# Netzteil_Darlington_v2.net
KiCad netlist of a schematic drawn in EAGLE
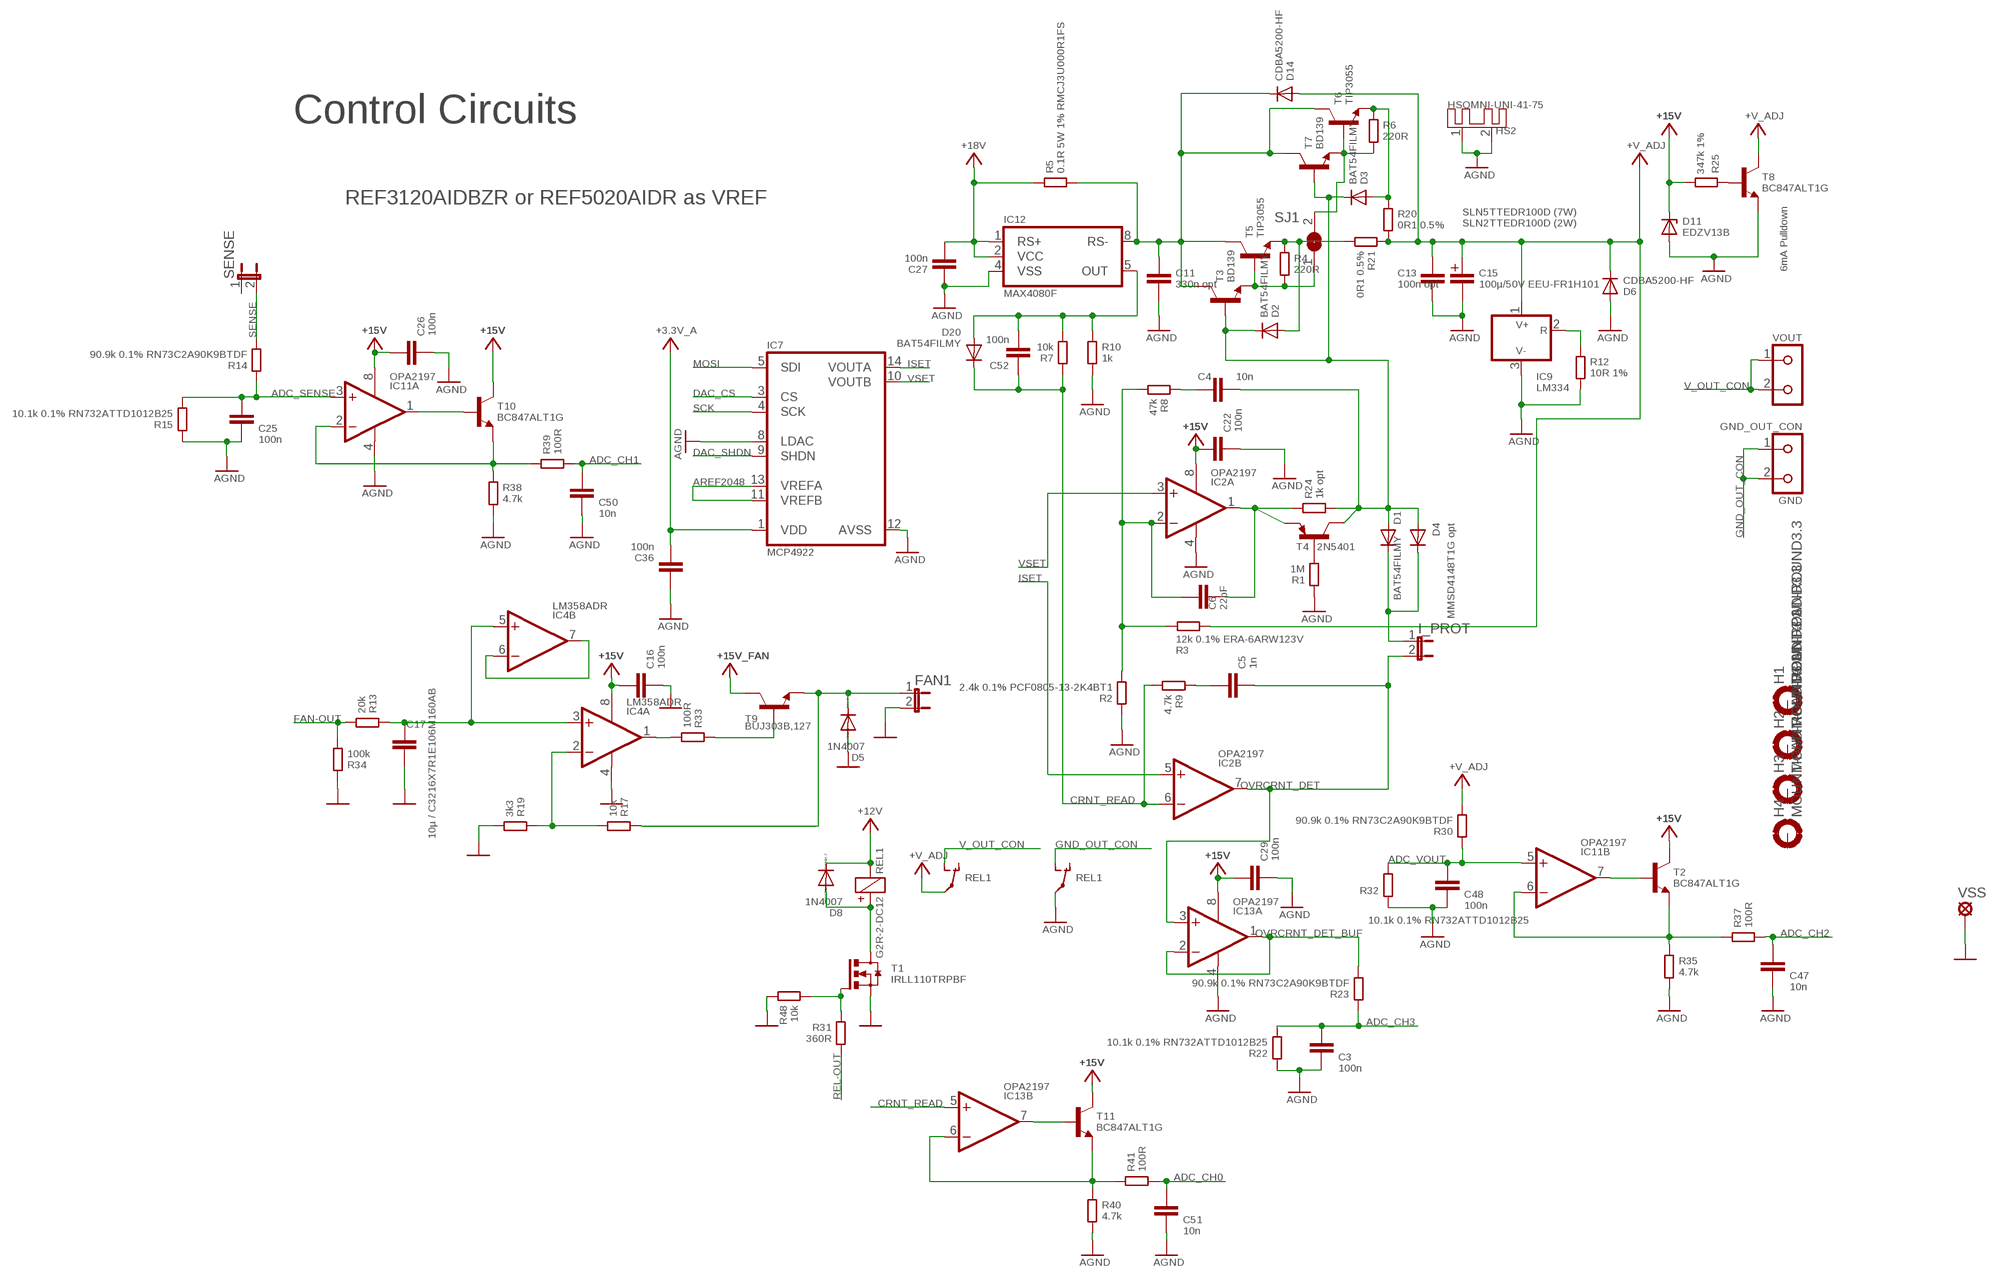
[diagram p0: schematic, sheet 1]
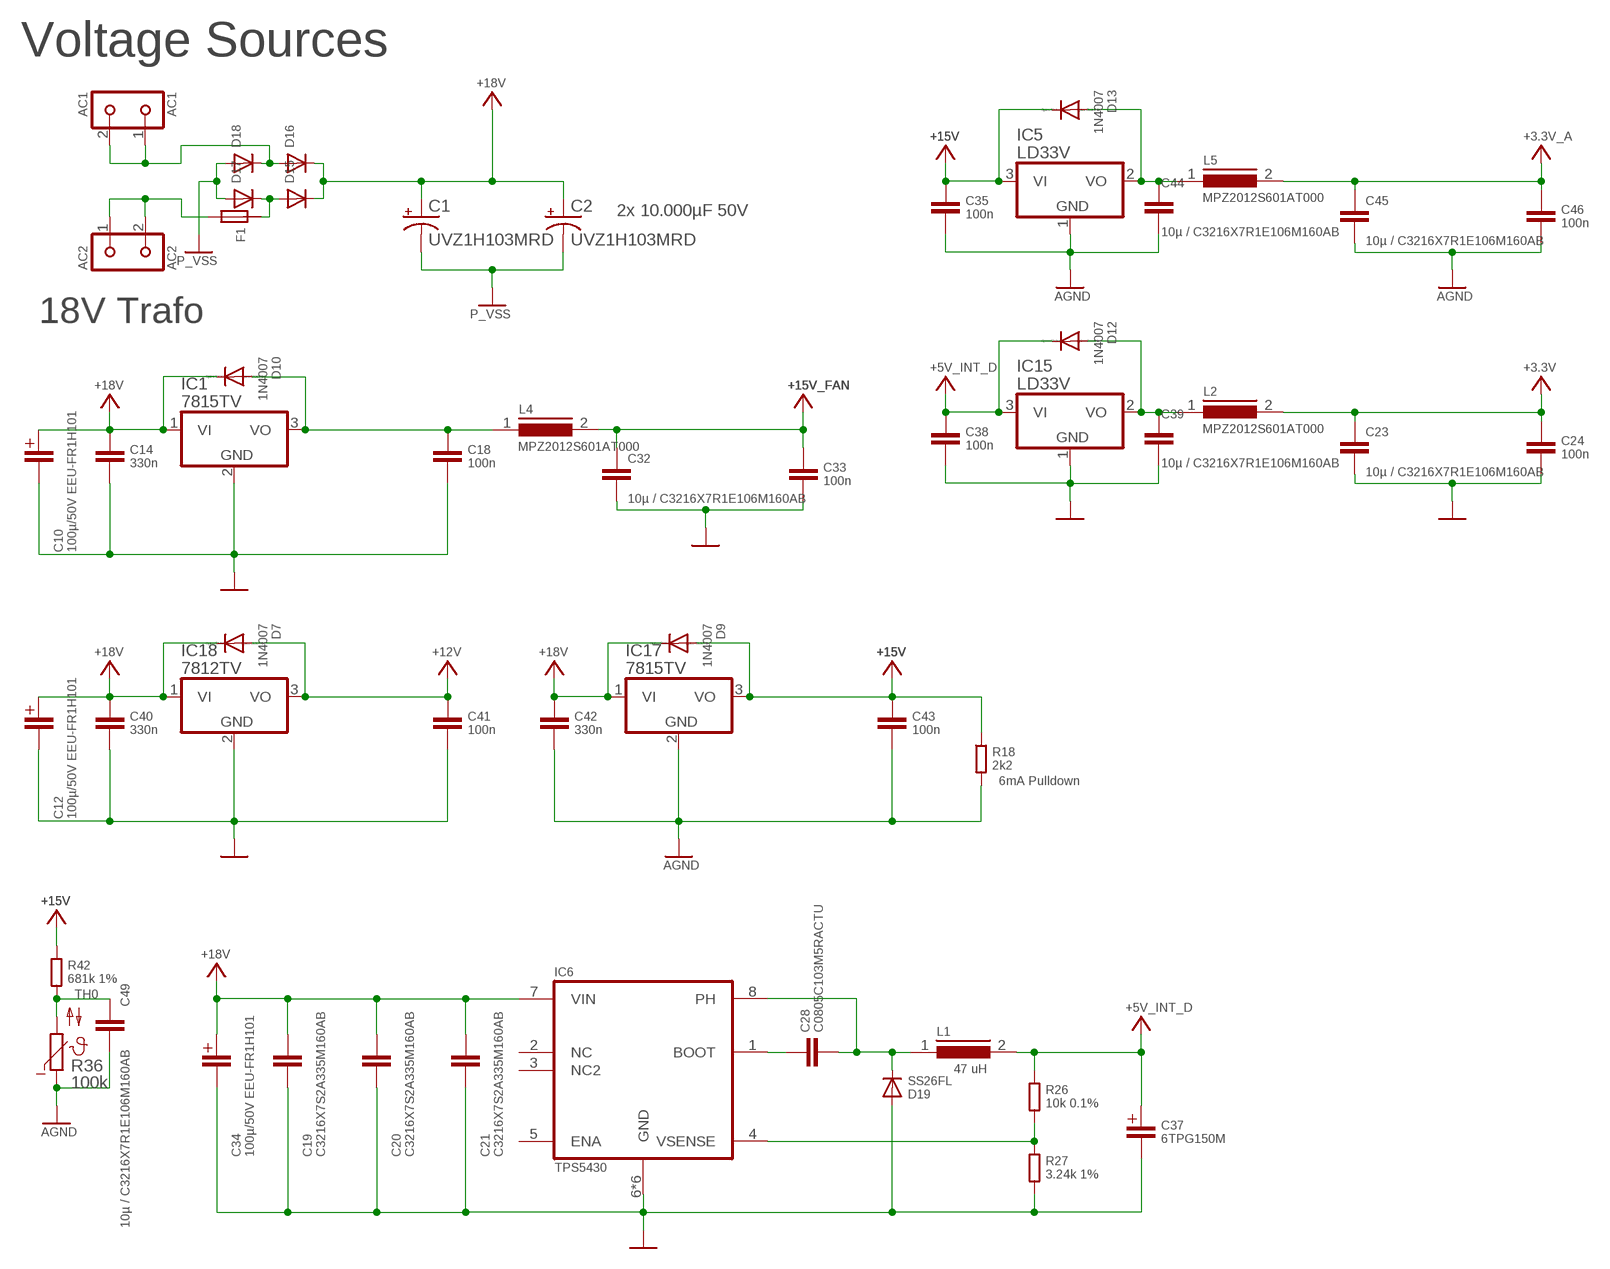
[diagram p1: schematic, sheet 2]
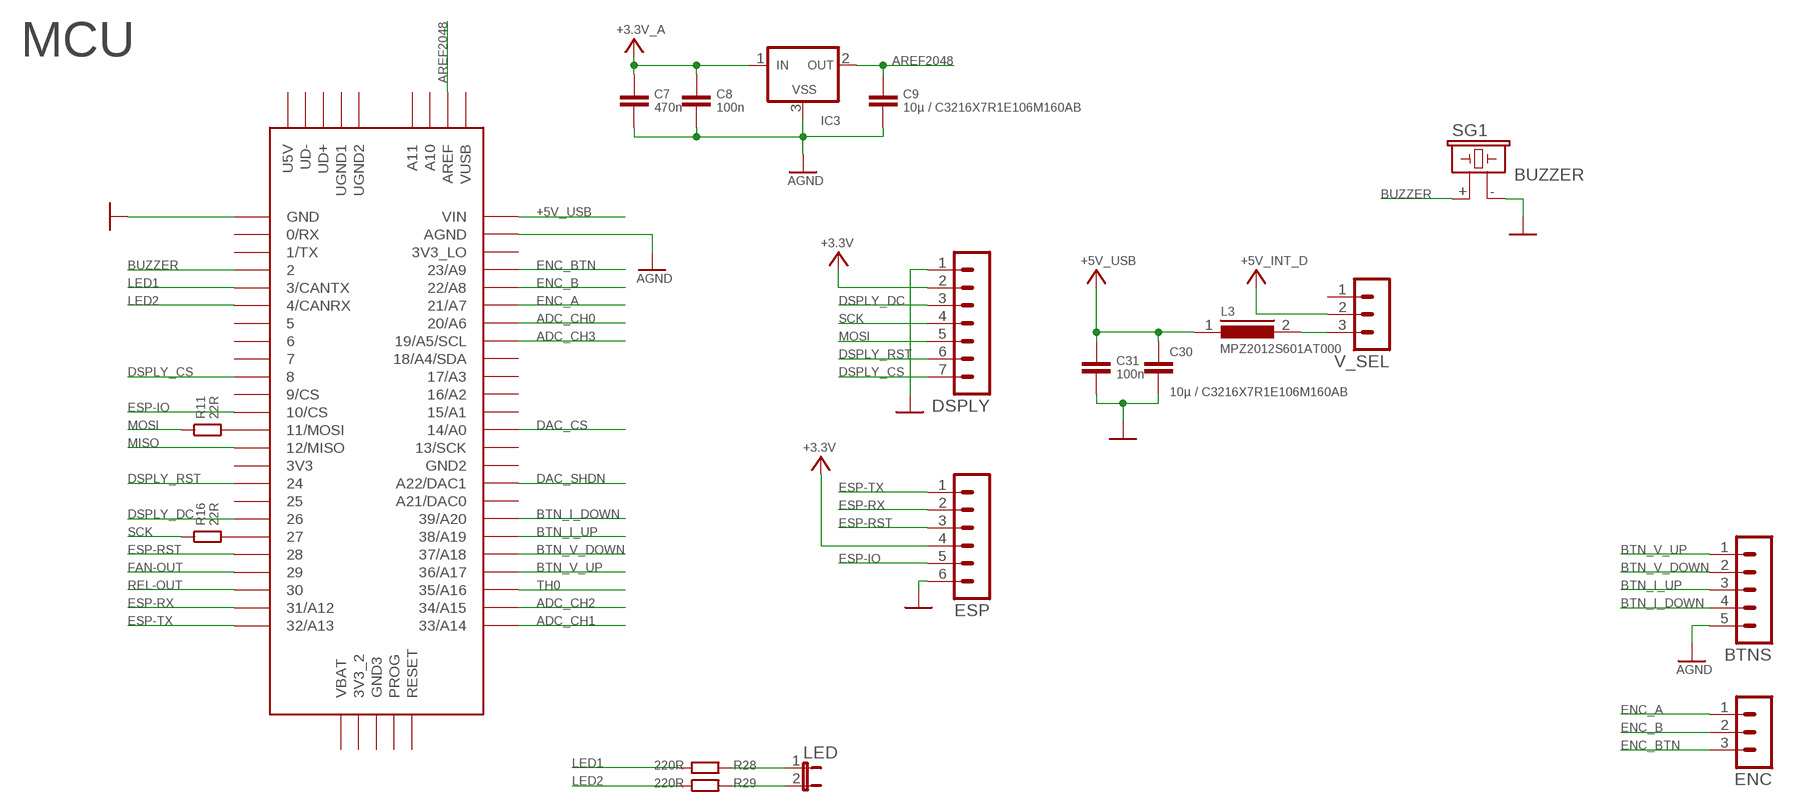
[diagram p2: schematic, sheet 3]

(export (version "E")
  (design (tool "Eeschema 10.0.6"))
  (components
    (comp (ref "C3")
      (value "100n")
      (footprint "eagle-import:0805")
      (libsource (lib "eagle-import") (part "CC/0805"))
    )
    (comp (ref "C4")
      (value "10n")
      (footprint "eagle-import:0805")
      (libsource (lib "eagle-import") (part "CC/0805"))
    )
    (comp (ref "C5")
      (value "1n")
      (footprint "eagle-import:0805")
      (libsource (lib "eagle-import") (part "CC/0805"))
    )
    (comp (ref "C6")
      (value "22pF")
      (footprint "eagle-import:0805")
      (libsource (lib "eagle-import") (part "CC/0805"))
    )
    (comp (ref "C11")
      (value "330n opt")
      (footprint "eagle-import:0805")
      (libsource (lib "eagle-import") (part "CC/0805"))
    )
    (comp (ref "C13")
      (value "100n opt")
      (footprint "eagle-import:0805")
      (libsource (lib "eagle-import") (part "CC/0805"))
    )
    (comp (ref "C15")
      (value "100µ/50V EEU-FR1H101")
      (footprint "eagle-import:C+_3.5_8")
      (libsource (lib "eagle-import") (part "C+3.5/8"))
    )
    (comp (ref "C16")
      (value "100n")
      (footprint "eagle-import:0805")
      (libsource (lib "eagle-import") (part "CC/0805"))
    )
    (comp (ref "C17")
      (value "10µ / C3216X7R1E106M160AB")
      (footprint "eagle-import:1206")
      (libsource (lib "eagle-import") (part "CC/1206"))
    )
    (comp (ref "C22")
      (value "100n")
      (footprint "eagle-import:0805")
      (libsource (lib "eagle-import") (part "CC/0805"))
    )
    (comp (ref "C25")
      (value "100n")
      (footprint "eagle-import:0805")
      (libsource (lib "eagle-import") (part "CC/0805"))
    )
    (comp (ref "C26")
      (value "100n")
      (footprint "eagle-import:0805")
      (libsource (lib "eagle-import") (part "CC/0805"))
    )
    (comp (ref "C27")
      (value "100n")
      (footprint "eagle-import:0805")
      (libsource (lib "eagle-import") (part "CC/0805"))
    )
    (comp (ref "C29")
      (value "100n")
      (footprint "eagle-import:0805")
      (libsource (lib "eagle-import") (part "CC/0805"))
    )
    (comp (ref "C36")
      (value "100n")
      (footprint "eagle-import:0805")
      (libsource (lib "eagle-import") (part "CC/0805"))
    )
    (comp (ref "C47")
      (value "10n")
      (footprint "eagle-import:0805")
      (libsource (lib "eagle-import") (part "CC/0805"))
    )
    (comp (ref "C48")
      (value "100n")
      (footprint "eagle-import:0805")
      (libsource (lib "eagle-import") (part "CC/0805"))
    )
    (comp (ref "C50")
      (value "10n")
      (footprint "eagle-import:0805")
      (libsource (lib "eagle-import") (part "CC/0805"))
    )
    (comp (ref "C51")
      (value "10n")
      (footprint "eagle-import:0805")
      (libsource (lib "eagle-import") (part "CC/0805"))
    )
    (comp (ref "C52")
      (value "100n")
      (footprint "eagle-import:0805")
      (libsource (lib "eagle-import") (part "CC/0805"))
    )
    (comp (ref "D1")
      (value "BAT54FILMY")
      (footprint "eagle-import:SOT23")
      (libsource (lib "eagle-import") (part "DBAT54FILMY"))
    )
    (comp (ref "D2")
      (value "BAT54FILMY")
      (footprint "eagle-import:SOT23")
      (libsource (lib "eagle-import") (part "DBAT54FILMY"))
    )
    (comp (ref "D3")
      (value "BAT54FILMY")
      (footprint "eagle-import:SOT23")
      (libsource (lib "eagle-import") (part "DBAT54FILMY"))
    )
    (comp (ref "D4")
      (value "MMSD4148T1G opt")
      (footprint "eagle-import:SOD-123")
      (libsource (lib "eagle-import") (part "DIODESOD-123"))
    )
    (comp (ref "D5")
      (value "1N4007")
      (footprint "eagle-import:DO214AA")
      (libsource (lib "eagle-import") (part "DIODE-DO214AA"))
    )
    (comp (ref "D6")
      (value "CDBA5200-HF")
      (footprint "eagle-import:DO214AC-2")
      (libsource (lib "eagle-import") (part "CDBA5200-HF"))
    )
    (comp (ref "D8")
      (value "1N4007")
      (footprint "eagle-import:DO214AA")
      (libsource (lib "eagle-import") (part "DIODE-DO214AA"))
    )
    (comp (ref "D11")
      (value "EDZV13B")
      (footprint "eagle-import:SOD-523")
      (libsource (lib "eagle-import") (part "ZD"))
    )
    (comp (ref "D14")
      (value "CDBA5200-HF")
      (footprint "eagle-import:DO214AC-2")
      (libsource (lib "eagle-import") (part "CDBA5200-HF"))
    )
    (comp (ref "D20")
      (value "BAT54FILMY")
      (footprint "eagle-import:SOT23")
      (libsource (lib "eagle-import") (part "DBAT54FILMY"))
    )
    (comp (ref "FAN1")
      (value "JP1E")
      (footprint "eagle-import:JP1")
      (libsource (lib "eagle-import") (part "JP1E"))
    )
    (comp (ref "GND_OUT_CON")
      (value "GND")
      (footprint "eagle-import:KL2-691311500002")
      (libsource (lib "eagle-import") (part "KL2691311500002"))
    )
    (comp (ref "H1")
      (value "MOUNT-PAD-ROUND3.3")
      (footprint "eagle-import:3,3-PAD")
      (libsource (lib "eagle-import") (part "MOUNT-PAD-ROUND3.3"))
    )
    (comp (ref "H2")
      (value "MOUNT-PAD-ROUND3.3")
      (footprint "eagle-import:3,3-PAD")
      (libsource (lib "eagle-import") (part "MOUNT-PAD-ROUND3.3"))
    )
    (comp (ref "H3")
      (value "MOUNT-PAD-ROUND3.3")
      (footprint "eagle-import:3,3-PAD")
      (libsource (lib "eagle-import") (part "MOUNT-PAD-ROUND3.3"))
    )
    (comp (ref "H4")
      (value "MOUNT-PAD-ROUND3.3")
      (footprint "eagle-import:3,3-PAD")
      (libsource (lib "eagle-import") (part "MOUNT-PAD-ROUND3.3"))
    )
    (comp (ref "HS2")
      (value "HSOMNI-UNI-41-75")
      (footprint "eagle-import:OMNI-UNI-41-75")
      (libsource (lib "eagle-import") (part "HSOMNI-UNI-41-75"))
    )
    (comp (ref "IC2")
      (value "OPA2197")
      (footprint "eagle-import:SOP8")
      (libsource (lib "eagle-import") (part "DUAL-OPVSOP8"))
    )
    (comp (ref "IC4")
      (value "LM358ADR")
      (footprint "eagle-import:SOP8")
      (libsource (lib "eagle-import") (part "DUAL-OPVSOP8"))
    )
    (comp (ref "IC7")
      (value "MCP4922")
      (footprint "eagle-import:TSSOP14")
      (libsource (lib "eagle-import") (part "MCP4922"))
    )
    (comp (ref "IC9")
      (value "LM334")
      (footprint "eagle-import:TO92-G")
      (libsource (lib "eagle-import") (part "LM334"))
    )
    (comp (ref "IC11")
      (value "OPA2197")
      (footprint "eagle-import:SOP8")
      (libsource (lib "eagle-import") (part "DUAL-OPVSOP8"))
    )
    (comp (ref "IC12")
      (value "MAX4080F")
      (footprint "eagle-import:SOP8")
      (libsource (lib "eagle-import") (part "MAX4080"))
    )
    (comp (ref "IC13")
      (value "OPA2197")
      (footprint "eagle-import:SOP8")
      (libsource (lib "eagle-import") (part "DUAL-OPVSOP8"))
    )
    (comp (ref "I_PROT")
      (value "JP1E")
      (footprint "eagle-import:JP1")
      (libsource (lib "eagle-import") (part "JP1E"))
    )
    (comp (ref "R1")
      (value "1M")
      (footprint "eagle-import:C0603K")
      (libsource (lib "eagle-import") (part "R-SMD0603"))
    )
    (comp (ref "R2")
      (value "2.4k 0.1% PCF0805-13-2K4BT1")
      (footprint "eagle-import:C0805K")
      (libsource (lib "eagle-import") (part "R-SMD0805"))
    )
    (comp (ref "R3")
      (value "12k 0.1% ERA-6ARW123V")
      (footprint "eagle-import:C0805K")
      (libsource (lib "eagle-import") (part "R-SMD0805"))
    )
    (comp (ref "R4")
      (value "220R")
      (footprint "eagle-import:C0805K")
      (libsource (lib "eagle-import") (part "R-SMD0805"))
    )
    (comp (ref "R5")
      (value "0.1R 5W 1% RMCJ3U000R1FS")
      (footprint "eagle-import:RMC-J3")
      (libsource (lib "eagle-import") (part "R-SHUNTRMC-J3"))
    )
    (comp (ref "R6")
      (value "220R")
      (footprint "eagle-import:C0805K")
      (libsource (lib "eagle-import") (part "R-SMD0805"))
    )
    (comp (ref "R7")
      (value "10k")
      (footprint "eagle-import:C0805K")
      (libsource (lib "eagle-import") (part "R-SMD0805"))
    )
    (comp (ref "R8")
      (value "47k")
      (footprint "eagle-import:C0805K")
      (libsource (lib "eagle-import") (part "R-SMD0805"))
    )
    (comp (ref "R9")
      (value "4.7k")
      (footprint "eagle-import:C0805K")
      (libsource (lib "eagle-import") (part "R-SMD0805"))
    )
    (comp (ref "R10")
      (value "1k")
      (footprint "eagle-import:C0805K")
      (libsource (lib "eagle-import") (part "R-SMD0805"))
    )
    (comp (ref "R12")
      (value "10R 1%")
      (footprint "eagle-import:C0805K")
      (libsource (lib "eagle-import") (part "R-SMD0805"))
    )
    (comp (ref "R13")
      (value "20k")
      (footprint "eagle-import:C0805K")
      (libsource (lib "eagle-import") (part "R-SMD0805"))
    )
    (comp (ref "R14")
      (value "90.9k 0.1% RN73C2A90K9BTDF")
      (footprint "eagle-import:C0805K")
      (libsource (lib "eagle-import") (part "R-SMD0805"))
    )
    (comp (ref "R15")
      (value "10.1k 0.1% RN732ATTD1012B25")
      (footprint "eagle-import:C0805K")
      (libsource (lib "eagle-import") (part "R-SMD0805"))
    )
    (comp (ref "R17")
      (value "10k")
      (footprint "eagle-import:C0805K")
      (libsource (lib "eagle-import") (part "R-SMD0805"))
    )
    (comp (ref "R19")
      (value "3k3")
      (footprint "eagle-import:C0805K")
      (libsource (lib "eagle-import") (part "R-SMD0805"))
    )
    (comp (ref "R20")
      (value "0R1 0.5%")
      (footprint "eagle-import:SLN2")
      (libsource (lib "eagle-import") (part "R-SMDSLN2"))
    )
    (comp (ref "R21")
      (value "0R1 0.5%")
      (footprint "eagle-import:SLN2")
      (libsource (lib "eagle-import") (part "R-SMDSLN2"))
    )
    (comp (ref "R22")
      (value "10.1k 0.1% RN732ATTD1012B25")
      (footprint "eagle-import:C0805K")
      (libsource (lib "eagle-import") (part "R-SMD0805"))
    )
    (comp (ref "R23")
      (value "90.9k 0.1% RN73C2A90K9BTDF")
      (footprint "eagle-import:C0805K")
      (libsource (lib "eagle-import") (part "R-SMD0805"))
    )
    (comp (ref "R24")
      (value "1k opt")
      (footprint "eagle-import:C0805K")
      (libsource (lib "eagle-import") (part "R-SMD0805"))
    )
    (comp (ref "R25")
      (value "347k 1%")
      (footprint "eagle-import:C0805K")
      (libsource (lib "eagle-import") (part "R-SMD0805"))
    )
    (comp (ref "R30")
      (value "90.9k 0.1% RN73C2A90K9BTDF")
      (footprint "eagle-import:C0805K")
      (libsource (lib "eagle-import") (part "R-SMD0805"))
    )
    (comp (ref "R31")
      (value "360R")
      (footprint "eagle-import:C0805K")
      (libsource (lib "eagle-import") (part "R-SMD0805"))
    )
    (comp (ref "R32")
      (value "10.1k 0.1% RN732ATTD1012B25")
      (footprint "eagle-import:C0805K")
      (libsource (lib "eagle-import") (part "R-SMD0805"))
    )
    (comp (ref "R33")
      (value "100R")
      (footprint "eagle-import:C0805K")
      (libsource (lib "eagle-import") (part "R-SMD0805"))
    )
    (comp (ref "R34")
      (value "100k")
      (footprint "eagle-import:C0805K")
      (libsource (lib "eagle-import") (part "R-SMD0805"))
    )
    (comp (ref "R35")
      (value "4.7k")
      (footprint "eagle-import:C0805K")
      (libsource (lib "eagle-import") (part "R-SMD0805"))
    )
    (comp (ref "R37")
      (value "100R")
      (footprint "eagle-import:C0805K")
      (libsource (lib "eagle-import") (part "R-SMD0805"))
    )
    (comp (ref "R38")
      (value "4.7k")
      (footprint "eagle-import:C0805K")
      (libsource (lib "eagle-import") (part "R-SMD0805"))
    )
    (comp (ref "R39")
      (value "100R")
      (footprint "eagle-import:C0805K")
      (libsource (lib "eagle-import") (part "R-SMD0805"))
    )
    (comp (ref "R40")
      (value "4.7k")
      (footprint "eagle-import:C0805K")
      (libsource (lib "eagle-import") (part "R-SMD0805"))
    )
    (comp (ref "R41")
      (value "100R")
      (footprint "eagle-import:C0805K")
      (libsource (lib "eagle-import") (part "R-SMD0805"))
    )
    (comp (ref "R48")
      (value "10k")
      (footprint "eagle-import:C0805K")
      (libsource (lib "eagle-import") (part "R-SMD0805"))
    )
    (comp (ref "REL1")
      (value "G2R-2-DC12")
      (footprint "eagle-import:REL-G2R2")
      (libsource (lib "eagle-import") (part "REL-2UG2R2"))
    )
    (comp (ref "SENSE")
      (value "JP1E")
      (footprint "eagle-import:JP1")
      (libsource (lib "eagle-import") (part "JP1E"))
    )
    (comp (ref "SJ1") (value "SJ") (footprint "eagle-import:SJ") (libsource (lib "eagle-import") (part "SJ")))
    (comp (ref "T1")
      (value "IRLL110TRPBF")
      (footprint "eagle-import:SOT223-4")
      (libsource (lib "eagle-import") (part "T-NMOSFDT457N"))
    )
    (comp (ref "T2")
      (value "BC847ALT1G")
      (footprint "eagle-import:SOT23-BEC")
      (libsource (lib "eagle-import") (part "T-NPNSOT23-BEC"))
    )
    (comp (ref "T3")
      (value "BD139")
      (footprint "eagle-import:TO126")
      (libsource (lib "eagle-import") (part "T-NPNTO126-ECB"))
    )
    (comp (ref "T4")
      (value "2N5401")
      (footprint "eagle-import:TO92-G")
      (libsource (lib "eagle-import") (part "T-PNPTO92-G-EBC"))
    )
    (comp (ref "T5")
      (value "TIP3055")
      (footprint "eagle-import:TOP3AV")
      (libsource (lib "eagle-import") (part "T-NPNTOP3AV-BCE"))
    )
    (comp (ref "T6")
      (value "TIP3055")
      (footprint "eagle-import:TOP3AV")
      (libsource (lib "eagle-import") (part "T-NPNTOP3AV-BCE"))
    )
    (comp (ref "T7")
      (value "BD139")
      (footprint "eagle-import:TO126")
      (libsource (lib "eagle-import") (part "T-NPNTO126-ECB"))
    )
    (comp (ref "T8")
      (value "BC847ALT1G")
      (footprint "eagle-import:SOT23-BEC")
      (libsource (lib "eagle-import") (part "T-NPNSOT23-BEC"))
    )
    (comp (ref "T9")
      (value "BUJ303B,127")
      (footprint "eagle-import:TO220V")
      (libsource (lib "eagle-import") (part "-NPN-TO220V"))
    )
    (comp (ref "T10")
      (value "BC847ALT1G")
      (footprint "eagle-import:SOT23-BEC")
      (libsource (lib "eagle-import") (part "T-NPNSOT23-BEC"))
    )
    (comp (ref "T11")
      (value "BC847ALT1G")
      (footprint "eagle-import:SOT23-BEC")
      (libsource (lib "eagle-import") (part "T-NPNSOT23-BEC"))
    )
    (comp (ref "VOUT")
      (value "KL2691311500002")
      (footprint "eagle-import:KL2-691311500002")
      (libsource (lib "eagle-import") (part "KL2691311500002"))
    )
    (comp (ref "VSS")
      (value "LSP13")
      (footprint "eagle-import:LSP13")
      (libsource (lib "eagle-import") (part "LSP13"))
    )
    (comp (ref "BTNS")
      (value "MA05-1")
      (footprint "eagle-import:MA05-1")
      (libsource (lib "eagle-import") (part "MA05-1"))
    )
    (comp (ref "C7")
      (value "470n")
      (footprint "eagle-import:0805")
      (libsource (lib "eagle-import") (part "CC/0805"))
    )
    (comp (ref "C8")
      (value "100n")
      (footprint "eagle-import:0805")
      (libsource (lib "eagle-import") (part "CC/0805"))
    )
    (comp (ref "C9")
      (value "10µ / C3216X7R1E106M160AB")
      (footprint "eagle-import:1206")
      (libsource (lib "eagle-import") (part "CC/1206"))
    )
    (comp (ref "C30")
      (value "10µ / C3216X7R1E106M160AB")
      (footprint "eagle-import:1206")
      (libsource (lib "eagle-import") (part "CC/1206"))
    )
    (comp (ref "C31")
      (value "100n")
      (footprint "eagle-import:0805")
      (libsource (lib "eagle-import") (part "CC/0805"))
    )
    (comp (ref "DSPLY")
      (value "MA07-1")
      (footprint "eagle-import:MA07-1")
      (libsource (lib "eagle-import") (part "MA07-1"))
    )
    (comp (ref "ENC")
      (value "MA03-1")
      (footprint "eagle-import:MA03-1")
      (libsource (lib "eagle-import") (part "MA03-1"))
    )
    (comp (ref "ESP")
      (value "MA06-1")
      (footprint "eagle-import:MA06-1")
      (libsource (lib "eagle-import") (part "MA06-1"))
    )
    (comp (ref "IC3")
      (value "REF3120")
      (footprint "eagle-import:SOT23")
      (libsource (lib "eagle-import") (part "REF3120"))
    )
    (comp (ref "L3")
      (value "MPZ2012S601AT000")
      (footprint "eagle-import:C0805K")
      (libsource (lib "eagle-import") (part "L0805"))
    )
    (comp (ref "LED")
      (value "JP1E")
      (footprint "eagle-import:JP1")
      (libsource (lib "eagle-import") (part "JP1E"))
    )
    (comp (ref "R11")
      (value "22R")
      (footprint "eagle-import:C0805K")
      (libsource (lib "eagle-import") (part "R-SMD0805"))
    )
    (comp (ref "R16")
      (value "22R")
      (footprint "eagle-import:C0805K")
      (libsource (lib "eagle-import") (part "R-SMD0805"))
    )
    (comp (ref "R28")
      (value "220R")
      (footprint "eagle-import:C0805K")
      (libsource (lib "eagle-import") (part "R-SMD0805"))
    )
    (comp (ref "R29")
      (value "220R")
      (footprint "eagle-import:C0805K")
      (libsource (lib "eagle-import") (part "R-SMD0805"))
    )
    (comp (ref "SG1")
      (value "BUZZER")
      (footprint "eagle-import:254-EMB73-RO")
      (libsource (lib "eagle-import") (part "BUZZER"))
    )
    (comp (ref "U$33")
      (value "TEENSY_3.5/3.6")
      (footprint "eagle-import:TEENSY_3.5_3.6")
      (libsource (lib "eagle-import") (part "TEENSY_3.5/3.6"))
    )
    (comp (ref "V_SEL")
      (value "MA03-1")
      (footprint "eagle-import:MA03-1")
      (libsource (lib "eagle-import") (part "MA03-1"))
    )
    (comp (ref "AC1")
      (value "AC1")
      (footprint "eagle-import:KL2-691311500002")
      (libsource (lib "eagle-import") (part "KL2691311500002"))
    )
    (comp (ref "AC2")
      (value "AC2")
      (footprint "eagle-import:KL2-691311500002")
      (libsource (lib "eagle-import") (part "KL2691311500002"))
    )
    (comp (ref "C1")
      (value "UVZ1H103MRD")
      (footprint "eagle-import:EB22,5D")
      (libsource (lib "eagle-import") (part "CPOL-USE10-22.5"))
    )
    (comp (ref "C2")
      (value "UVZ1H103MRD")
      (footprint "eagle-import:EB22,5D")
      (libsource (lib "eagle-import") (part "CPOL-USE10-22.5"))
    )
    (comp (ref "C10")
      (value "100µ/50V EEU-FR1H101")
      (footprint "eagle-import:C+_3.5_8")
      (libsource (lib "eagle-import") (part "C+3.5/8"))
    )
    (comp (ref "C12")
      (value "100µ/50V EEU-FR1H101")
      (footprint "eagle-import:C+_3.5_8")
      (libsource (lib "eagle-import") (part "C+3.5/8"))
    )
    (comp (ref "C14")
      (value "330n")
      (footprint "eagle-import:0805")
      (libsource (lib "eagle-import") (part "CC/0805"))
    )
    (comp (ref "C18")
      (value "100n")
      (footprint "eagle-import:0805")
      (libsource (lib "eagle-import") (part "CC/0805"))
    )
    (comp (ref "C19")
      (value "C3216X7S2A335M160AB")
      (footprint "eagle-import:1206")
      (libsource (lib "eagle-import") (part "CC/1206"))
    )
    (comp (ref "C20")
      (value "C3216X7S2A335M160AB")
      (footprint "eagle-import:1206")
      (libsource (lib "eagle-import") (part "CC/1206"))
    )
    (comp (ref "C21")
      (value "C3216X7S2A335M160AB")
      (footprint "eagle-import:1206")
      (libsource (lib "eagle-import") (part "CC/1206"))
    )
    (comp (ref "C23")
      (value "10µ / C3216X7R1E106M160AB")
      (footprint "eagle-import:1206")
      (libsource (lib "eagle-import") (part "CC/1206"))
    )
    (comp (ref "C24")
      (value "100n")
      (footprint "eagle-import:0805")
      (libsource (lib "eagle-import") (part "CC/0805"))
    )
    (comp (ref "C28")
      (value "C0805C103M5RACTU")
      (footprint "eagle-import:0805")
      (libsource (lib "eagle-import") (part "CC/0805"))
    )
    (comp (ref "C32")
      (value "10µ / C3216X7R1E106M160AB")
      (footprint "eagle-import:1206")
      (libsource (lib "eagle-import") (part "CC/1206"))
    )
    (comp (ref "C33")
      (value "100n")
      (footprint "eagle-import:0805")
      (libsource (lib "eagle-import") (part "CC/0805"))
    )
    (comp (ref "C34")
      (value "100µ/50V EEU-FR1H101")
      (footprint "eagle-import:C+_3.5_8")
      (libsource (lib "eagle-import") (part "C+3.5/8"))
    )
    (comp (ref "C35")
      (value "100n")
      (footprint "eagle-import:0805")
      (libsource (lib "eagle-import") (part "CC/0805"))
    )
    (comp (ref "C37")
      (value "6TPG150M")
      (footprint "eagle-import:CT1210")
      (libsource (lib "eagle-import") (part "C-TANTAL"))
    )
    (comp (ref "C38")
      (value "100n")
      (footprint "eagle-import:0805")
      (libsource (lib "eagle-import") (part "CC/0805"))
    )
    (comp (ref "C39")
      (value "10µ / C3216X7R1E106M160AB")
      (footprint "eagle-import:1206")
      (libsource (lib "eagle-import") (part "CC/1206"))
    )
    (comp (ref "C40")
      (value "330n")
      (footprint "eagle-import:0805")
      (libsource (lib "eagle-import") (part "CC/0805"))
    )
    (comp (ref "C41")
      (value "100n")
      (footprint "eagle-import:0805")
      (libsource (lib "eagle-import") (part "CC/0805"))
    )
    (comp (ref "C42")
      (value "330n")
      (footprint "eagle-import:0805")
      (libsource (lib "eagle-import") (part "CC/0805"))
    )
    (comp (ref "C43")
      (value "100n")
      (footprint "eagle-import:0805")
      (libsource (lib "eagle-import") (part "CC/0805"))
    )
    (comp (ref "C44")
      (value "10µ / C3216X7R1E106M160AB")
      (footprint "eagle-import:1206")
      (libsource (lib "eagle-import") (part "CC/1206"))
    )
    (comp (ref "C45")
      (value "10µ / C3216X7R1E106M160AB")
      (footprint "eagle-import:1206")
      (libsource (lib "eagle-import") (part "CC/1206"))
    )
    (comp (ref "C46")
      (value "100n")
      (footprint "eagle-import:0805")
      (libsource (lib "eagle-import") (part "CC/0805"))
    )
    (comp (ref "C49")
      (value "10µ / C3216X7R1E106M160AB")
      (footprint "eagle-import:1206")
      (libsource (lib "eagle-import") (part "CC/1206"))
    )
    (comp (ref "D7")
      (value "1N4007")
      (footprint "eagle-import:DO214AA")
      (libsource (lib "eagle-import") (part "DIODE-DO214AA"))
    )
    (comp (ref "D9")
      (value "1N4007")
      (footprint "eagle-import:DO214AA")
      (libsource (lib "eagle-import") (part "DIODE-DO214AA"))
    )
    (comp (ref "D10")
      (value "1N4007")
      (footprint "eagle-import:DO214AA")
      (libsource (lib "eagle-import") (part "DIODE-DO214AA"))
    )
    (comp (ref "D12")
      (value "1N4007")
      (footprint "eagle-import:DO214AA")
      (libsource (lib "eagle-import") (part "DIODE-DO214AA"))
    )
    (comp (ref "D13")
      (value "1N4007")
      (footprint "eagle-import:DO214AA")
      (libsource (lib "eagle-import") (part "DIODE-DO214AA"))
    )
    (comp (ref "D15")
      (value "DTO263-PWR")
      (footprint "eagle-import:TO-263AB-PWR")
      (libsource (lib "eagle-import") (part "DTO263-PWR"))
    )
    (comp (ref "D16")
      (value "DTO263-PWR")
      (footprint "eagle-import:TO-263AB-PWR")
      (libsource (lib "eagle-import") (part "DTO263-PWR"))
    )
    (comp (ref "D17")
      (value "DTO263-PWR")
      (footprint "eagle-import:TO-263AB-PWR")
      (libsource (lib "eagle-import") (part "DTO263-PWR"))
    )
    (comp (ref "D18")
      (value "DTO263-PWR")
      (footprint "eagle-import:TO-263AB-PWR")
      (libsource (lib "eagle-import") (part "DTO263-PWR"))
    )
    (comp (ref "D19")
      (value "SS26FL")
      (footprint "eagle-import:SOD-123")
      (libsource (lib "eagle-import") (part "DSOD123"))
    )
    (comp (ref "F1")
      (value "F5X20")
      (footprint "eagle-import:F5X20")
      (libsource (lib "eagle-import") (part "F5X20"))
    )
    (comp (ref "IC1")
      (value "7815TV")
      (footprint "eagle-import:TO220V")
      (libsource (lib "eagle-import") (part "78TV15"))
    )
    (comp (ref "IC5")
      (value "LD33V")
      (footprint "eagle-import:TO220V")
      (libsource (lib "eagle-import") (part "LD33V"))
    )
    (comp (ref "IC6")
      (value "TPS5430")
      (footprint "eagle-import:SOIC8POWERPAD")
      (libsource (lib "eagle-import") (part "TPS5430"))
    )
    (comp (ref "IC15")
      (value "LD33V")
      (footprint "eagle-import:TO220V")
      (libsource (lib "eagle-import") (part "LD33V"))
    )
    (comp (ref "IC17")
      (value "7815TV")
      (footprint "eagle-import:TO220V")
      (libsource (lib "eagle-import") (part "78TV15"))
    )
    (comp (ref "IC18")
      (value "7812TV")
      (footprint "eagle-import:TO220V")
      (libsource (lib "eagle-import") (part "78TV12"))
    )
    (comp (ref "L1")
      (value "47 uH")
      (footprint "eagle-import:WE-PD")
      (libsource (lib "eagle-import") (part "L744771147"))
    )
    (comp (ref "L2")
      (value "MPZ2012S601AT000")
      (footprint "eagle-import:C0805K")
      (libsource (lib "eagle-import") (part "L0805"))
    )
    (comp (ref "L4")
      (value "MPZ2012S601AT000")
      (footprint "eagle-import:C0805K")
      (libsource (lib "eagle-import") (part "L0805"))
    )
    (comp (ref "L5")
      (value "MPZ2012S601AT000")
      (footprint "eagle-import:C0805K")
      (libsource (lib "eagle-import") (part "L0805"))
    )
    (comp (ref "R18")
      (value "2k2")
      (footprint "eagle-import:C0805K")
      (libsource (lib "eagle-import") (part "R-SMD0805"))
    )
    (comp (ref "R26")
      (value "10k 0.1%")
      (footprint "eagle-import:C0805K")
      (libsource (lib "eagle-import") (part "R-SMD0805"))
    )
    (comp (ref "R27")
      (value "3.24k 1%")
      (footprint "eagle-import:C0805K")
      (libsource (lib "eagle-import") (part "R-SMD0805"))
    )
    (comp (ref "R36")
      (value "100k")
      (footprint "eagle-import:P640")
      (libsource (lib "eagle-import") (part "NTC640"))
    )
    (comp (ref "R42")
      (value "681k 1%")
      (footprint "eagle-import:C0603K")
      (libsource (lib "eagle-import") (part "R-SMD0603"))
    )
  )
  (nets
    (net (code "1") (name "+3.3V") (class "Default")
      (node (ref "C23") (pin "1") (pinfunction "1_1") (pintype "passive"))
      (node (ref "C24") (pin "1") (pinfunction "1_1") (pintype "passive"))
      (node (ref "DSPLY") (pin "2") (pinfunction "2_2") (pintype "passive"))
      (node (ref "ESP") (pin "4") (pinfunction "4_4") (pintype "passive"))
      (node (ref "L2") (pin "2") (pinfunction "2_2") (pintype "passive"))
    )
    (net (code "2") (name "+3.3V_A") (class "Default")
      (node (ref "C36") (pin "2") (pinfunction "2_2") (pintype "passive"))
      (node (ref "C45") (pin "1") (pinfunction "1_1") (pintype "passive"))
      (node (ref "C46") (pin "1") (pinfunction "1_1") (pintype "passive"))
      (node (ref "C7") (pin "1") (pinfunction "1_1") (pintype "passive"))
      (node (ref "C8") (pin "1") (pinfunction "1_1") (pintype "passive"))
      (node (ref "IC3") (pin "1") (pinfunction "IN_1") (pintype "power_in"))
      (node (ref "IC7") (pin "1") (pinfunction "VDD_1") (pintype "power_in"))
      (node (ref "L5") (pin "2") (pinfunction "2_2") (pintype "passive"))
    )
    (net (code "3") (name "+5V_INT_D") (class "Default")
      (node (ref "C37") (pin "+") (pinfunction "+_+") (pintype "passive"))
      (node (ref "C38") (pin "1") (pinfunction "1_1") (pintype "passive"))
      (node (ref "D12") (pin "C") (pinfunction "C_C") (pintype "passive"))
      (node (ref "IC15") (pin "3") (pinfunction "VI_3") (pintype "input"))
      (node (ref "L1") (pin "2") (pinfunction "2_2") (pintype "passive"))
      (node (ref "R26") (pin "1") (pinfunction "1_1") (pintype "passive"))
      (node (ref "V_SEL") (pin "2") (pinfunction "2_2") (pintype "passive"))
    )
    (net (code "4") (name "+5V_USB") (class "Default")
      (node (ref "C30") (pin "1") (pinfunction "1_1") (pintype "passive"))
      (node (ref "C31") (pin "1") (pinfunction "1_1") (pintype "passive"))
      (node (ref "L3") (pin "1") (pinfunction "1_1") (pintype "passive"))
      (node (ref "U$33") (pin "VIN") (pinfunction "VIN_VIN") (pintype "bidirectional"))
    )
    (net (code "5") (name "+12V") (class "Default")
      (node (ref "C41") (pin "1") (pinfunction "1_1") (pintype "passive"))
      (node (ref "D7") (pin "A") (pinfunction "A_A") (pintype "passive"))
      (node (ref "D8") (pin "C") (pinfunction "C_C") (pintype "passive"))
      (node (ref "IC18") (pin "3") (pinfunction "VO_3") (pintype "passive"))
      (node (ref "REL1") (pin "-") (pinfunction "-_-") (pintype "passive"))
    )
    (net (code "6") (name "+15V") (class "Default")
      (node (ref "C16") (pin "1") (pinfunction "1_1") (pintype "passive"))
      (node (ref "C22") (pin "1") (pinfunction "1_1") (pintype "passive"))
      (node (ref "C26") (pin "1") (pinfunction "1_1") (pintype "passive"))
      (node (ref "C29") (pin "1") (pinfunction "1_1") (pintype "passive"))
      (node (ref "C35") (pin "1") (pinfunction "1_1") (pintype "passive"))
      (node (ref "C43") (pin "1") (pinfunction "1_1") (pintype "passive"))
      (node (ref "D11") (pin "C") (pinfunction "C_C") (pintype "passive"))
      (node (ref "D13") (pin "C") (pinfunction "C_C") (pintype "passive"))
      (node (ref "D9") (pin "A") (pinfunction "A_A") (pintype "passive"))
      (node (ref "IC11") (pin "8") (pinfunction "V+_8") (pintype "power_in"))
      (node (ref "IC13") (pin "8") (pinfunction "V+_8") (pintype "power_in"))
      (node (ref "IC17") (pin "3") (pinfunction "VO_3") (pintype "passive"))
      (node (ref "IC2") (pin "8") (pinfunction "V+_8") (pintype "power_in"))
      (node (ref "IC4") (pin "8") (pinfunction "V+_8") (pintype "power_in"))
      (node (ref "IC5") (pin "3") (pinfunction "VI_3") (pintype "input"))
      (node (ref "R18") (pin "1") (pinfunction "1_1") (pintype "passive"))
      (node (ref "R25") (pin "2") (pinfunction "2_2") (pintype "passive"))
      (node (ref "R42") (pin "1") (pinfunction "1_1") (pintype "passive"))
      (node (ref "T10") (pin "C") (pinfunction "C_C") (pintype "passive"))
      (node (ref "T11") (pin "C") (pinfunction "C_C") (pintype "passive"))
      (node (ref "T2") (pin "C") (pinfunction "C_C") (pintype "passive"))
    )
    (net (code "7") (name "+15V_FAN") (class "Default")
      (node (ref "C32") (pin "1") (pinfunction "1_1") (pintype "passive"))
      (node (ref "C33") (pin "1") (pinfunction "1_1") (pintype "passive"))
      (node (ref "L4") (pin "2") (pinfunction "2_2") (pintype "passive"))
      (node (ref "T9") (pin "2") (pinfunction "C_2") (pintype "passive"))
    )
    (net (code "8") (name "+18V") (class "Default")
      (node (ref "C1") (pin "+") (pinfunction "+_+") (pintype "passive"))
      (node (ref "C10") (pin "+") (pinfunction "+_+") (pintype "passive"))
      (node (ref "C12") (pin "+") (pinfunction "+_+") (pintype "passive"))
      (node (ref "C14") (pin "1") (pinfunction "1_1") (pintype "passive"))
      (node (ref "C19") (pin "1") (pinfunction "1_1") (pintype "passive"))
      (node (ref "C2") (pin "+") (pinfunction "+_+") (pintype "passive"))
      (node (ref "C20") (pin "1") (pinfunction "1_1") (pintype "passive"))
      (node (ref "C21") (pin "1") (pinfunction "1_1") (pintype "passive"))
      (node (ref "C27") (pin "2") (pinfunction "2_2") (pintype "passive"))
      (node (ref "C34") (pin "+") (pinfunction "+_+") (pintype "passive"))
      (node (ref "C40") (pin "1") (pinfunction "1_1") (pintype "passive"))
      (node (ref "C42") (pin "1") (pinfunction "1_1") (pintype "passive"))
      (node (ref "D10") (pin "C") (pinfunction "C_C") (pintype "passive"))
      (node (ref "D15") (pin "2") (pinfunction "C_2") (pintype "passive"))
      (node (ref "D15") (pin "2_PWR1") (pinfunction "C_2_PWR1") (pintype "passive"))
      (node (ref "D15") (pin "2_PWR10") (pinfunction "C_2_PWR10") (pintype "passive"))
      (node (ref "D15") (pin "2_PWR11") (pinfunction "C_2_PWR11") (pintype "passive"))
      (node (ref "D15") (pin "2_PWR12") (pinfunction "C_2_PWR12") (pintype "passive"))
      (node (ref "D15") (pin "2_PWR2") (pinfunction "C_2_PWR2") (pintype "passive"))
      (node (ref "D15") (pin "2_PWR3") (pinfunction "C_2_PWR3") (pintype "passive"))
      (node (ref "D15") (pin "2_PWR4") (pinfunction "C_2_PWR4") (pintype "passive"))
      (node (ref "D15") (pin "2_PWR5") (pinfunction "C_2_PWR5") (pintype "passive"))
      (node (ref "D15") (pin "2_PWR6") (pinfunction "C_2_PWR6") (pintype "passive"))
      (node (ref "D15") (pin "2_PWR7") (pinfunction "C_2_PWR7") (pintype "passive"))
      (node (ref "D15") (pin "2_PWR8") (pinfunction "C_2_PWR8") (pintype "passive"))
      (node (ref "D15") (pin "2_PWR9") (pinfunction "C_2_PWR9") (pintype "passive"))
      (node (ref "D16") (pin "2") (pinfunction "C_2") (pintype "passive"))
      (node (ref "D16") (pin "2_PWR1") (pinfunction "C_2_PWR1") (pintype "passive"))
      (node (ref "D16") (pin "2_PWR10") (pinfunction "C_2_PWR10") (pintype "passive"))
      (node (ref "D16") (pin "2_PWR11") (pinfunction "C_2_PWR11") (pintype "passive"))
      (node (ref "D16") (pin "2_PWR12") (pinfunction "C_2_PWR12") (pintype "passive"))
      (node (ref "D16") (pin "2_PWR2") (pinfunction "C_2_PWR2") (pintype "passive"))
      (node (ref "D16") (pin "2_PWR3") (pinfunction "C_2_PWR3") (pintype "passive"))
      (node (ref "D16") (pin "2_PWR4") (pinfunction "C_2_PWR4") (pintype "passive"))
      (node (ref "D16") (pin "2_PWR5") (pinfunction "C_2_PWR5") (pintype "passive"))
      (node (ref "D16") (pin "2_PWR6") (pinfunction "C_2_PWR6") (pintype "passive"))
      (node (ref "D16") (pin "2_PWR7") (pinfunction "C_2_PWR7") (pintype "passive"))
      (node (ref "D16") (pin "2_PWR8") (pinfunction "C_2_PWR8") (pintype "passive"))
      (node (ref "D16") (pin "2_PWR9") (pinfunction "C_2_PWR9") (pintype "passive"))
      (node (ref "D7") (pin "C") (pinfunction "C_C") (pintype "passive"))
      (node (ref "D9") (pin "C") (pinfunction "C_C") (pintype "passive"))
      (node (ref "IC1") (pin "1") (pinfunction "VI_1") (pintype "input"))
      (node (ref "IC12") (pin "1") (pinfunction "RS+_1") (pintype "input"))
      (node (ref "IC12") (pin "2") (pinfunction "VCC_2") (pintype "power_in"))
      (node (ref "IC17") (pin "1") (pinfunction "VI_1") (pintype "input"))
      (node (ref "IC18") (pin "1") (pinfunction "VI_1") (pintype "input"))
      (node (ref "IC6") (pin "7") (pinfunction "VIN_7") (pintype "power_in"))
      (node (ref "R5") (pin "1") (pinfunction "1_1") (pintype "passive"))
    )
    (net (code "9") (name "+V_ADJ") (class "Default")
      (node (ref "C13") (pin "1") (pinfunction "1_1") (pintype "passive"))
      (node (ref "C15") (pin "+") (pinfunction "+_+") (pintype "passive"))
      (node (ref "D14") (pin "A") (pinfunction "A_A") (pintype "passive"))
      (node (ref "D6") (pin "C") (pinfunction "C_C") (pintype "passive"))
      (node (ref "IC9") (pin "1") (pinfunction "V+_1") (pintype "passive"))
      (node (ref "R20") (pin "2") (pinfunction "2_2") (pintype "passive"))
      (node (ref "R21") (pin "1") (pinfunction "1_1") (pintype "passive"))
      (node (ref "R3") (pin "1") (pinfunction "1_1") (pintype "passive"))
      (node (ref "R30") (pin "2") (pinfunction "2_2") (pintype "passive"))
      (node (ref "REL1") (pin "P1") (pinfunction "P_P1") (pintype "passive"))
      (node (ref "T8") (pin "C") (pinfunction "C_C") (pintype "passive"))
    )
    (net (code "10") (name "ADC_CH0") (class "Default")
      (node (ref "C51") (pin "1") (pinfunction "1_1") (pintype "passive"))
      (node (ref "R41") (pin "2") (pinfunction "2_2") (pintype "passive"))
      (node (ref "U$33") (pin "20/A6") (pinfunction "20/A6_20/A6") (pintype "bidirectional"))
    )
    (net (code "11") (name "ADC_CH1") (class "Default")
      (node (ref "C50") (pin "1") (pinfunction "1_1") (pintype "passive"))
      (node (ref "R39") (pin "2") (pinfunction "2_2") (pintype "passive"))
      (node (ref "U$33") (pin "33/A14") (pinfunction "33/A14_33/A14") (pintype "bidirectional"))
    )
    (net (code "12") (name "ADC_CH2") (class "Default")
      (node (ref "C47") (pin "1") (pinfunction "1_1") (pintype "passive"))
      (node (ref "R37") (pin "2") (pinfunction "2_2") (pintype "passive"))
      (node (ref "U$33") (pin "34/A15") (pinfunction "34/A15_34/A15") (pintype "bidirectional"))
    )
    (net (code "13") (name "ADC_CH3") (class "Default")
      (node (ref "C3") (pin "1") (pinfunction "1_1") (pintype "passive"))
      (node (ref "R22") (pin "2") (pinfunction "2_2") (pintype "passive"))
      (node (ref "R23") (pin "1") (pinfunction "1_1") (pintype "passive"))
      (node (ref "U$33") (pin "19/A5/SCL") (pinfunction "19/A5/SCL_19/A5/SCL") (pintype "bidirectional"))
    )
    (net (code "14") (name "ADC_SENSE") (class "Default")
      (node (ref "C25") (pin "1") (pinfunction "1_1") (pintype "passive"))
      (node (ref "IC11") (pin "3") (pinfunction "+IN_3") (pintype "input"))
      (node (ref "R14") (pin "1") (pinfunction "1_1") (pintype "passive"))
      (node (ref "R15") (pin "2") (pinfunction "2_2") (pintype "passive"))
    )
    (net (code "15") (name "ADC_VOUT") (class "Default")
      (node (ref "C48") (pin "1") (pinfunction "1_1") (pintype "passive"))
      (node (ref "IC11") (pin "5") (pinfunction "+IN_5") (pintype "input"))
      (node (ref "R30") (pin "1") (pinfunction "1_1") (pintype "passive"))
      (node (ref "R32") (pin "2") (pinfunction "2_2") (pintype "passive"))
    )
    (net (code "16") (name "AGND") (class "Default")
      (node (ref "BTNS") (pin "5") (pinfunction "5_5") (pintype "passive"))
      (node (ref "C11") (pin "2") (pinfunction "2_2") (pintype "passive"))
      (node (ref "C13") (pin "2") (pinfunction "2_2") (pintype "passive"))
      (node (ref "C15") (pin "-") (pinfunction "-_-") (pintype "passive"))
      (node (ref "C22") (pin "2") (pinfunction "2_2") (pintype "passive"))
      (node (ref "C25") (pin "2") (pinfunction "2_2") (pintype "passive"))
      (node (ref "C26") (pin "2") (pinfunction "2_2") (pintype "passive"))
      (node (ref "C27") (pin "1") (pinfunction "1_1") (pintype "passive"))
      (node (ref "C29") (pin "2") (pinfunction "2_2") (pintype "passive"))
      (node (ref "C3") (pin "2") (pinfunction "2_2") (pintype "passive"))
      (node (ref "C35") (pin "2") (pinfunction "2_2") (pintype "passive"))
      (node (ref "C36") (pin "1") (pinfunction "1_1") (pintype "passive"))
      (node (ref "C42") (pin "2") (pinfunction "2_2") (pintype "passive"))
      (node (ref "C43") (pin "2") (pinfunction "2_2") (pintype "passive"))
      (node (ref "C44") (pin "1") (pinfunction "1_1") (pintype "passive"))
      (node (ref "C45") (pin "2") (pinfunction "2_2") (pintype "passive"))
      (node (ref "C46") (pin "2") (pinfunction "2_2") (pintype "passive"))
      (node (ref "C47") (pin "2") (pinfunction "2_2") (pintype "passive"))
      (node (ref "C48") (pin "2") (pinfunction "2_2") (pintype "passive"))
      (node (ref "C49") (pin "1") (pinfunction "1_1") (pintype "passive"))
      (node (ref "C50") (pin "2") (pinfunction "2_2") (pintype "passive"))
      (node (ref "C51") (pin "2") (pinfunction "2_2") (pintype "passive"))
      (node (ref "C7") (pin "2") (pinfunction "2_2") (pintype "passive"))
      (node (ref "C8") (pin "2") (pinfunction "2_2") (pintype "passive"))
      (node (ref "C9") (pin "2") (pinfunction "2_2") (pintype "passive"))
      (node (ref "D11") (pin "A") (pinfunction "A_A") (pintype "passive"))
      (node (ref "D6") (pin "A") (pinfunction "A_A") (pintype "passive"))
      (node (ref "HS2") (pin "1") (pinfunction "1_1") (pintype "passive"))
      (node (ref "HS2") (pin "2") (pinfunction "2_2") (pintype "passive"))
      (node (ref "IC11") (pin "4") (pinfunction "V-_4") (pintype "power_in"))
      (node (ref "IC12") (pin "4") (pinfunction "VSS_4") (pintype "power_in"))
      (node (ref "IC13") (pin "4") (pinfunction "V-_4") (pintype "power_in"))
      (node (ref "IC17") (pin "2") (pinfunction "GND_2") (pintype "passive"))
      (node (ref "IC2") (pin "4") (pinfunction "V-_4") (pintype "power_in"))
      (node (ref "IC3") (pin "3") (pinfunction "VSS_3") (pintype "power_in"))
      (node (ref "IC5") (pin "1") (pinfunction "GND_1") (pintype "passive"))
      (node (ref "IC7") (pin "12") (pinfunction "AVSS_12") (pintype "power_in"))
      (node (ref "IC7") (pin "8") (pinfunction "LDAC_8") (pintype "input"))
      (node (ref "IC9") (pin "3") (pinfunction "V-_3") (pintype "passive"))
      (node (ref "R1") (pin "1") (pinfunction "1_1") (pintype "passive"))
      (node (ref "R10") (pin "2") (pinfunction "2_2") (pintype "passive"))
      (node (ref "R12") (pin "2") (pinfunction "2_2") (pintype "passive"))
      (node (ref "R15") (pin "1") (pinfunction "1_1") (pintype "passive"))
      (node (ref "R18") (pin "2") (pinfunction "2_2") (pintype "passive"))
      (node (ref "R2") (pin "1") (pinfunction "1_1") (pintype "passive"))
      (node (ref "R22") (pin "1") (pinfunction "1_1") (pintype "passive"))
      (node (ref "R32") (pin "1") (pinfunction "1_1") (pintype "passive"))
      (node (ref "R35") (pin "2") (pinfunction "2_2") (pintype "passive"))
      (node (ref "R36") (pin "1") (pinfunction "1_1") (pintype "passive"))
      (node (ref "R38") (pin "2") (pinfunction "2_2") (pintype "passive"))
      (node (ref "R40") (pin "2") (pinfunction "2_2") (pintype "passive"))
      (node (ref "REL1") (pin "P2") (pinfunction "P_P2") (pintype "passive"))
      (node (ref "T8") (pin "E") (pinfunction "E_E") (pintype "passive"))
      (node (ref "U$33") (pin "AGND") (pinfunction "AGND_AGND") (pintype "bidirectional"))
    )
    (net (code "17") (name "AREF2048") (class "Default")
      (node (ref "C9") (pin "1") (pinfunction "1_1") (pintype "passive"))
      (node (ref "IC3") (pin "2") (pinfunction "OUT_2") (pintype "output"))
      (node (ref "IC7") (pin "11") (pinfunction "VREFB_11") (pintype "input"))
      (node (ref "IC7") (pin "13") (pinfunction "VREFA_13") (pintype "input"))
      (node (ref "U$33") (pin "AREF") (pinfunction "AREF_AREF") (pintype "bidirectional"))
    )
    (net (code "18") (name "BTN_I_DOWN") (class "Default")
      (node (ref "BTNS") (pin "4") (pinfunction "4_4") (pintype "passive"))
      (node (ref "U$33") (pin "39/A20") (pinfunction "39/A20_39/A20") (pintype "bidirectional"))
    )
    (net (code "19") (name "BTN_I_UP") (class "Default")
      (node (ref "BTNS") (pin "3") (pinfunction "3_3") (pintype "passive"))
      (node (ref "U$33") (pin "38/A19") (pinfunction "38/A19_38/A19") (pintype "bidirectional"))
    )
    (net (code "20") (name "BTN_V_DOWN") (class "Default")
      (node (ref "BTNS") (pin "2") (pinfunction "2_2") (pintype "passive"))
      (node (ref "U$33") (pin "37/A18") (pinfunction "37/A18_37/A18") (pintype "bidirectional"))
    )
    (net (code "21") (name "BTN_V_UP") (class "Default")
      (node (ref "BTNS") (pin "1") (pinfunction "1_1") (pintype "passive"))
      (node (ref "U$33") (pin "36/A17") (pinfunction "36/A17_36/A17") (pintype "bidirectional"))
    )
    (net (code "22") (name "BUZZER") (class "Default")
      (node (ref "SG1") (pin "+") (pinfunction "1_+") (pintype "passive"))
      (node (ref "U$33") (pin "2") (pinfunction "2_2") (pintype "bidirectional"))
    )
    (net (code "23") (name "CRNT_READ") (class "Default")
      (node (ref "C52") (pin "1") (pinfunction "1_1") (pintype "passive"))
      (node (ref "D20") (pin "3") (pinfunction "C_3") (pintype "passive"))
      (node (ref "IC13") (pin "5") (pinfunction "+IN_5") (pintype "input"))
      (node (ref "IC2") (pin "6") (pinfunction "-IN_6") (pintype "input"))
      (node (ref "R7") (pin "1") (pinfunction "1_1") (pintype "passive"))
      (node (ref "R9") (pin "2") (pinfunction "2_2") (pintype "passive"))
    )
    (net (code "24") (name "DAC_CS") (class "Default")
      (node (ref "IC7") (pin "3") (pinfunction "CS_3") (pintype "input"))
      (node (ref "U$33") (pin "14/A0") (pinfunction "14/A0_14/A0") (pintype "bidirectional"))
    )
    (net (code "25") (name "DAC_SHDN") (class "Default")
      (node (ref "IC7") (pin "9") (pinfunction "SHDN_9") (pintype "input"))
      (node (ref "U$33") (pin "A22/DAC1") (pinfunction "A22/DAC1_A22/DAC1") (pintype "bidirectional"))
    )
    (net (code "26") (name "DSPLY_CS") (class "Default")
      (node (ref "DSPLY") (pin "7") (pinfunction "7_7") (pintype "passive"))
      (node (ref "U$33") (pin "8") (pinfunction "8_8") (pintype "bidirectional"))
    )
    (net (code "27") (name "DSPLY_DC") (class "Default")
      (node (ref "DSPLY") (pin "3") (pinfunction "3_3") (pintype "passive"))
      (node (ref "U$33") (pin "26") (pinfunction "26_26") (pintype "bidirectional"))
    )
    (net (code "28") (name "DSPLY_RST") (class "Default")
      (node (ref "DSPLY") (pin "6") (pinfunction "6_6") (pintype "passive"))
      (node (ref "U$33") (pin "24") (pinfunction "24_24") (pintype "bidirectional"))
    )
    (net (code "29") (name "ENC_A") (class "Default")
      (node (ref "ENC") (pin "1") (pinfunction "1_1") (pintype "passive"))
      (node (ref "U$33") (pin "21/A7") (pinfunction "21/A7_21/A7") (pintype "bidirectional"))
    )
    (net (code "30") (name "ENC_B") (class "Default")
      (node (ref "ENC") (pin "2") (pinfunction "2_2") (pintype "passive"))
      (node (ref "U$33") (pin "22/A8") (pinfunction "22/A8_22/A8") (pintype "bidirectional"))
    )
    (net (code "31") (name "ENC_BTN") (class "Default")
      (node (ref "ENC") (pin "3") (pinfunction "3_3") (pintype "passive"))
      (node (ref "U$33") (pin "23/A9") (pinfunction "23/A9_23/A9") (pintype "bidirectional"))
    )
    (net (code "32") (name "ESP-IO") (class "Default")
      (node (ref "ESP") (pin "5") (pinfunction "5_5") (pintype "passive"))
      (node (ref "U$33") (pin "10/CS") (pinfunction "10/CS_10/CS") (pintype "bidirectional"))
    )
    (net (code "33") (name "ESP-RST") (class "Default")
      (node (ref "ESP") (pin "3") (pinfunction "3_3") (pintype "passive"))
      (node (ref "U$33") (pin "28") (pinfunction "28_28") (pintype "bidirectional"))
    )
    (net (code "34") (name "ESP-RX") (class "Default")
      (node (ref "ESP") (pin "2") (pinfunction "2_2") (pintype "passive"))
      (node (ref "U$33") (pin "31/A12") (pinfunction "31/A12_31/A12") (pintype "bidirectional"))
    )
    (net (code "35") (name "ESP-TX") (class "Default")
      (node (ref "ESP") (pin "1") (pinfunction "1_1") (pintype "passive"))
      (node (ref "U$33") (pin "32/A13") (pinfunction "32/A13_32/A13") (pintype "bidirectional"))
    )
    (net (code "36") (name "FAN-OUT") (class "Default")
      (node (ref "R13") (pin "2") (pinfunction "2_2") (pintype "passive"))
      (node (ref "R34") (pin "2") (pinfunction "2_2") (pintype "passive"))
      (node (ref "U$33") (pin "29") (pinfunction "29_29") (pintype "bidirectional"))
    )
    (net (code "37") (name "GND_OUT_CON") (class "Default")
      (node (ref "GND_OUT_CON") (pin "1") (pinfunction "1_1") (pintype "passive"))
      (node (ref "GND_OUT_CON") (pin "2") (pinfunction "2_2") (pintype "passive"))
      (node (ref "REL1") (pin "S2") (pinfunction "S_S2") (pintype "passive"))
    )
    (net (code "38") (name "ISET") (class "Default")
      (node (ref "IC2") (pin "5") (pinfunction "+IN_5") (pintype "input"))
      (node (ref "IC7") (pin "14") (pinfunction "VOUTA_14") (pintype "output"))
    )
    (net (code "39") (name "LED1") (class "Default")
      (node (ref "R28") (pin "1") (pinfunction "1_1") (pintype "passive"))
      (node (ref "U$33") (pin "3/CANTX") (pinfunction "3/CANTX_3/CANTX") (pintype "bidirectional"))
    )
    (net (code "40") (name "LED2") (class "Default")
      (node (ref "R29") (pin "1") (pinfunction "1_1") (pintype "passive"))
      (node (ref "U$33") (pin "4/CANRX") (pinfunction "4/CANRX_4/CANRX") (pintype "bidirectional"))
    )
    (net (code "41") (name "MISO") (class "Default")
      (node (ref "U$33") (pin "12/MISO") (pinfunction "12/MISO_12/MISO") (pintype "bidirectional"))
    )
    (net (code "42") (name "MOSI") (class "Default")
      (node (ref "DSPLY") (pin "5") (pinfunction "5_5") (pintype "passive"))
      (node (ref "IC7") (pin "5") (pinfunction "SDI_5") (pintype "input"))
      (node (ref "R11") (pin "1") (pinfunction "1_1") (pintype "passive"))
    )
    (net (code "43") (name "Net-(AC1-Pad1)") (class "Default")
      (node (ref "AC1") (pin "1") (pinfunction "1_1") (pintype "passive"))
      (node (ref "AC1") (pin "2") (pinfunction "2_2") (pintype "passive"))
      (node (ref "D16") (pin "1") (pinfunction "A_1") (pintype "passive"))
      (node (ref "D16") (pin "3") (pinfunction "A_3") (pintype "passive"))
      (node (ref "D18") (pin "2") (pinfunction "C_2") (pintype "passive"))
      (node (ref "D18") (pin "2_PWR1") (pinfunction "C_2_PWR1") (pintype "passive"))
      (node (ref "D18") (pin "2_PWR10") (pinfunction "C_2_PWR10") (pintype "passive"))
      (node (ref "D18") (pin "2_PWR11") (pinfunction "C_2_PWR11") (pintype "passive"))
      (node (ref "D18") (pin "2_PWR12") (pinfunction "C_2_PWR12") (pintype "passive"))
      (node (ref "D18") (pin "2_PWR2") (pinfunction "C_2_PWR2") (pintype "passive"))
      (node (ref "D18") (pin "2_PWR3") (pinfunction "C_2_PWR3") (pintype "passive"))
      (node (ref "D18") (pin "2_PWR4") (pinfunction "C_2_PWR4") (pintype "passive"))
      (node (ref "D18") (pin "2_PWR5") (pinfunction "C_2_PWR5") (pintype "passive"))
      (node (ref "D18") (pin "2_PWR6") (pinfunction "C_2_PWR6") (pintype "passive"))
      (node (ref "D18") (pin "2_PWR7") (pinfunction "C_2_PWR7") (pintype "passive"))
      (node (ref "D18") (pin "2_PWR8") (pinfunction "C_2_PWR8") (pintype "passive"))
      (node (ref "D18") (pin "2_PWR9") (pinfunction "C_2_PWR9") (pintype "passive"))
    )
    (net (code "44") (name "Net-(AC2-Pad1)") (class "Default")
      (node (ref "AC2") (pin "1") (pinfunction "1_1") (pintype "passive"))
      (node (ref "AC2") (pin "2") (pinfunction "2_2") (pintype "passive"))
      (node (ref "F1") (pin "3") (pinfunction "2_3") (pintype "passive"))
      (node (ref "F1") (pin "4") (pinfunction "2_4") (pintype "passive"))
    )
    (net (code "45") (name "Net-(C4-Pad1)") (class "Default")
      (node (ref "C4") (pin "1") (pinfunction "1_1") (pintype "passive"))
      (node (ref "R8") (pin "1") (pinfunction "1_1") (pintype "passive"))
    )
    (net (code "46") (name "Net-(C5-Pad1)") (class "Default")
      (node (ref "C5") (pin "1") (pinfunction "1_1") (pintype "passive"))
      (node (ref "R9") (pin "1") (pinfunction "1_1") (pintype "passive"))
    )
    (net (code "47") (name "Net-(D1-A)") (class "Default")
      (node (ref "C4") (pin "2") (pinfunction "2_2") (pintype "passive"))
      (node (ref "D1") (pin "1") (pinfunction "A_1") (pintype "passive"))
      (node (ref "D2") (pin "3") (pinfunction "C_3") (pintype "passive"))
      (node (ref "D3") (pin "3") (pinfunction "C_3") (pintype "passive"))
      (node (ref "D4") (pin "A") (pinfunction "A_A") (pintype "passive"))
      (node (ref "R24") (pin "2") (pinfunction "2_2") (pintype "passive"))
      (node (ref "T3") (pin "3") (pinfunction "B_3") (pintype "passive"))
      (node (ref "T4") (pin "3") (pinfunction "C_3") (pintype "passive"))
      (node (ref "T7") (pin "3") (pinfunction "B_3") (pintype "passive"))
    )
    (net (code "48") (name "Net-(D1-C)") (class "Default")
      (node (ref "D1") (pin "3") (pinfunction "C_3") (pintype "passive"))
      (node (ref "D4") (pin "C") (pinfunction "C_C") (pintype "passive"))
      (node (ref "I_PROT") (pin "1") (pinfunction "1_1") (pintype "passive"))
    )
    (net (code "49") (name "Net-(D2-A)") (class "Default")
      (node (ref "D2") (pin "1") (pinfunction "A_1") (pintype "passive"))
      (node (ref "R21") (pin "2") (pinfunction "2_2") (pintype "passive"))
      (node (ref "R4") (pin "1") (pinfunction "1_1") (pintype "passive"))
      (node (ref "T5") (pin "E") (pinfunction "E_E") (pintype "passive"))
    )
    (net (code "50") (name "Net-(D3-A)") (class "Default")
      (node (ref "D3") (pin "1") (pinfunction "A_1") (pintype "passive"))
      (node (ref "R20") (pin "1") (pinfunction "1_1") (pintype "passive"))
      (node (ref "R6") (pin "1") (pinfunction "1_1") (pintype "passive"))
      (node (ref "T6") (pin "E") (pinfunction "E_E") (pintype "passive"))
    )
    (net (code "51") (name "Net-(D8-PadA)") (class "Default")
      (node (ref "D8") (pin "A") (pinfunction "A_A") (pintype "passive"))
      (node (ref "REL1") (pin "+") (pinfunction "+_+") (pintype "passive"))
      (node (ref "T1") (pin "2") (pinfunction "D_2") (pintype "passive"))
      (node (ref "T1") (pin "4") (pinfunction "D_4") (pintype "passive"))
    )
    (net (code "52") (name "Net-(D15-A-Pad1)") (class "Default")
      (node (ref "D15") (pin "1") (pinfunction "A_1") (pintype "passive"))
      (node (ref "D15") (pin "3") (pinfunction "A_3") (pintype "passive"))
      (node (ref "D17") (pin "2") (pinfunction "C_2") (pintype "passive"))
      (node (ref "D17") (pin "2_PWR1") (pinfunction "C_2_PWR1") (pintype "passive"))
      (node (ref "D17") (pin "2_PWR10") (pinfunction "C_2_PWR10") (pintype "passive"))
      (node (ref "D17") (pin "2_PWR11") (pinfunction "C_2_PWR11") (pintype "passive"))
      (node (ref "D17") (pin "2_PWR12") (pinfunction "C_2_PWR12") (pintype "passive"))
      (node (ref "D17") (pin "2_PWR2") (pinfunction "C_2_PWR2") (pintype "passive"))
      (node (ref "D17") (pin "2_PWR3") (pinfunction "C_2_PWR3") (pintype "passive"))
      (node (ref "D17") (pin "2_PWR4") (pinfunction "C_2_PWR4") (pintype "passive"))
      (node (ref "D17") (pin "2_PWR5") (pinfunction "C_2_PWR5") (pintype "passive"))
      (node (ref "D17") (pin "2_PWR6") (pinfunction "C_2_PWR6") (pintype "passive"))
      (node (ref "D17") (pin "2_PWR7") (pinfunction "C_2_PWR7") (pintype "passive"))
      (node (ref "D17") (pin "2_PWR8") (pinfunction "C_2_PWR8") (pintype "passive"))
      (node (ref "D17") (pin "2_PWR9") (pinfunction "C_2_PWR9") (pintype "passive"))
      (node (ref "F1") (pin "1") (pinfunction "1_1") (pintype "passive"))
      (node (ref "F1") (pin "2") (pinfunction "1_2") (pintype "passive"))
    )
    (net (code "53") (name "Net-(D19-C)") (class "Default")
      (node (ref "C28") (pin "2") (pinfunction "2_2") (pintype "passive"))
      (node (ref "D19") (pin "-") (pinfunction "C_-") (pintype "passive"))
      (node (ref "IC6") (pin "8") (pinfunction "PH_8") (pintype "bidirectional"))
      (node (ref "L1") (pin "1") (pinfunction "1_1") (pintype "passive"))
    )
    (net (code "54") (name "Net-(D20-A)") (class "Default")
      (node (ref "C52") (pin "2") (pinfunction "2_2") (pintype "passive"))
      (node (ref "D20") (pin "1") (pinfunction "A_1") (pintype "passive"))
      (node (ref "IC12") (pin "5") (pinfunction "OUT_5") (pintype "bidirectional"))
      (node (ref "R10") (pin "1") (pinfunction "1_1") (pintype "passive"))
      (node (ref "R7") (pin "2") (pinfunction "2_2") (pintype "passive"))
    )
    (net (code "55") (name "Net-(IC1-VO)") (class "Default")
      (node (ref "C18") (pin "1") (pinfunction "1_1") (pintype "passive"))
      (node (ref "D10") (pin "A") (pinfunction "A_A") (pintype "passive"))
      (node (ref "IC1") (pin "3") (pinfunction "VO_3") (pintype "passive"))
      (node (ref "L4") (pin "1") (pinfunction "1_1") (pintype "passive"))
    )
    (net (code "56") (name "Net-(IC2A--IN)") (class "Default")
      (node (ref "C6") (pin "1") (pinfunction "1_1") (pintype "passive"))
      (node (ref "IC2") (pin "2") (pinfunction "-IN_2") (pintype "input"))
      (node (ref "R2") (pin "2") (pinfunction "2_2") (pintype "passive"))
      (node (ref "R3") (pin "2") (pinfunction "2_2") (pintype "passive"))
      (node (ref "R8") (pin "2") (pinfunction "2_2") (pintype "passive"))
    )
    (net (code "57") (name "Net-(IC2A-OUT)") (class "Default")
      (node (ref "C6") (pin "2") (pinfunction "2_2") (pintype "passive"))
      (node (ref "IC2") (pin "1") (pinfunction "OUT_1") (pintype "output"))
      (node (ref "R24") (pin "1") (pinfunction "1_1") (pintype "passive"))
      (node (ref "T4") (pin "1") (pinfunction "E_1") (pintype "passive"))
    )
    (net (code "58") (name "Net-(IC4A-+IN)") (class "Default")
      (node (ref "C17") (pin "2") (pinfunction "2_2") (pintype "passive"))
      (node (ref "IC4") (pin "3") (pinfunction "+IN_3") (pintype "input"))
      (node (ref "IC4") (pin "5") (pinfunction "+IN_5") (pintype "input"))
      (node (ref "R13") (pin "1") (pinfunction "1_1") (pintype "passive"))
    )
    (net (code "59") (name "Net-(IC4A--IN)") (class "Default")
      (node (ref "IC4") (pin "2") (pinfunction "-IN_2") (pintype "input"))
      (node (ref "R17") (pin "2") (pinfunction "2_2") (pintype "passive"))
      (node (ref "R19") (pin "1") (pinfunction "1_1") (pintype "passive"))
    )
    (net (code "60") (name "Net-(IC4A-OUT)") (class "Default")
      (node (ref "IC4") (pin "1") (pinfunction "OUT_1") (pintype "output"))
      (node (ref "R33") (pin "2") (pinfunction "2_2") (pintype "passive"))
    )
    (net (code "61") (name "Net-(IC4B--IN)") (class "Default")
      (node (ref "IC4") (pin "6") (pinfunction "-IN_6") (pintype "input"))
      (node (ref "IC4") (pin "7") (pinfunction "OUT_7") (pintype "output"))
    )
    (net (code "62") (name "Net-(IC5-VO)") (class "Default")
      (node (ref "C44") (pin "2") (pinfunction "2_2") (pintype "passive"))
      (node (ref "D13") (pin "A") (pinfunction "A_A") (pintype "passive"))
      (node (ref "IC5") (pin "2") (pinfunction "VO_2") (pintype "passive"))
      (node (ref "L5") (pin "1") (pinfunction "1_1") (pintype "passive"))
    )
    (net (code "63") (name "Net-(IC6-BOOT)") (class "Default")
      (node (ref "C28") (pin "1") (pinfunction "1_1") (pintype "passive"))
      (node (ref "IC6") (pin "1") (pinfunction "BOOT_1") (pintype "bidirectional"))
    )
    (net (code "64") (name "Net-(IC6-VSENSE)") (class "Default")
      (node (ref "IC6") (pin "4") (pinfunction "VSENSE_4") (pintype "input"))
      (node (ref "R26") (pin "2") (pinfunction "2_2") (pintype "passive"))
      (node (ref "R27") (pin "1") (pinfunction "1_1") (pintype "passive"))
    )
    (net (code "65") (name "Net-(IC9-R)") (class "Default")
      (node (ref "IC9") (pin "2") (pinfunction "R_2") (pintype "input"))
      (node (ref "R12") (pin "1") (pinfunction "1_1") (pintype "passive"))
    )
    (net (code "66") (name "Net-(IC11A--IN)") (class "Default")
      (node (ref "IC11") (pin "2") (pinfunction "-IN_2") (pintype "input"))
      (node (ref "R38") (pin "1") (pinfunction "1_1") (pintype "passive"))
      (node (ref "R39") (pin "1") (pinfunction "1_1") (pintype "passive"))
      (node (ref "T10") (pin "E") (pinfunction "E_E") (pintype "passive"))
    )
    (net (code "67") (name "Net-(IC11A-OUT)") (class "Default")
      (node (ref "IC11") (pin "1") (pinfunction "OUT_1") (pintype "output"))
      (node (ref "T10") (pin "B") (pinfunction "B_B") (pintype "passive"))
    )
    (net (code "68") (name "Net-(IC11B--IN)") (class "Default")
      (node (ref "IC11") (pin "6") (pinfunction "-IN_6") (pintype "input"))
      (node (ref "R35") (pin "1") (pinfunction "1_1") (pintype "passive"))
      (node (ref "R37") (pin "1") (pinfunction "1_1") (pintype "passive"))
      (node (ref "T2") (pin "E") (pinfunction "E_E") (pintype "passive"))
    )
    (net (code "69") (name "Net-(IC11B-OUT)") (class "Default")
      (node (ref "IC11") (pin "7") (pinfunction "OUT_7") (pintype "output"))
      (node (ref "T2") (pin "B") (pinfunction "B_B") (pintype "passive"))
    )
    (net (code "70") (name "Net-(IC12-RS-)") (class "Default")
      (node (ref "C11") (pin "1") (pinfunction "1_1") (pintype "passive"))
      (node (ref "D14") (pin "C") (pinfunction "C_C") (pintype "passive"))
      (node (ref "IC12") (pin "8") (pinfunction "RS-_8") (pintype "input"))
      (node (ref "R5") (pin "2") (pinfunction "2_2") (pintype "passive"))
      (node (ref "T3") (pin "2") (pinfunction "C_2") (pintype "passive"))
      (node (ref "T5") (pin "C") (pinfunction "C_C") (pintype "passive"))
      (node (ref "T6") (pin "C") (pinfunction "C_C") (pintype "passive"))
      (node (ref "T7") (pin "2") (pinfunction "C_2") (pintype "passive"))
    )
    (net (code "71") (name "Net-(IC13B--IN)") (class "Default")
      (node (ref "IC13") (pin "6") (pinfunction "-IN_6") (pintype "input"))
      (node (ref "R40") (pin "1") (pinfunction "1_1") (pintype "passive"))
      (node (ref "R41") (pin "1") (pinfunction "1_1") (pintype "passive"))
      (node (ref "T11") (pin "E") (pinfunction "E_E") (pintype "passive"))
    )
    (net (code "72") (name "Net-(IC13B-OUT)") (class "Default")
      (node (ref "IC13") (pin "7") (pinfunction "OUT_7") (pintype "output"))
      (node (ref "T11") (pin "B") (pinfunction "B_B") (pintype "passive"))
    )
    (net (code "73") (name "Net-(IC15-VO)") (class "Default")
      (node (ref "C39") (pin "2") (pinfunction "2_2") (pintype "passive"))
      (node (ref "D12") (pin "A") (pinfunction "A_A") (pintype "passive"))
      (node (ref "IC15") (pin "2") (pinfunction "VO_2") (pintype "passive"))
      (node (ref "L2") (pin "1") (pinfunction "1_1") (pintype "passive"))
    )
    (net (code "74") (name "Net-(L3-Pad2)") (class "Default")
      (node (ref "L3") (pin "2") (pinfunction "2_2") (pintype "passive"))
      (node (ref "V_SEL") (pin "3") (pinfunction "3_3") (pintype "passive"))
    )
    (net (code "75") (name "Net-(LED-Pad1)") (class "Default")
      (node (ref "LED") (pin "1") (pinfunction "1_1") (pintype "passive"))
      (node (ref "R28") (pin "2") (pinfunction "2_2") (pintype "passive"))
    )
    (net (code "76") (name "Net-(LED-Pad2)") (class "Default")
      (node (ref "LED") (pin "2") (pinfunction "2_2") (pintype "passive"))
      (node (ref "R29") (pin "2") (pinfunction "2_2") (pintype "passive"))
    )
    (net (code "77") (name "Net-(R11-Pad2)") (class "Default")
      (node (ref "R11") (pin "2") (pinfunction "2_2") (pintype "passive"))
      (node (ref "U$33") (pin "11/MOSI") (pinfunction "11/MOSI_11/MOSI") (pintype "bidirectional"))
    )
    (net (code "78") (name "Net-(R16-Pad2)") (class "Default")
      (node (ref "R16") (pin "2") (pinfunction "2_2") (pintype "passive"))
      (node (ref "U$33") (pin "27") (pinfunction "27_27") (pintype "bidirectional"))
    )
    (net (code "79") (name "Net-(R25-Pad1)") (class "Default")
      (node (ref "R25") (pin "1") (pinfunction "1_1") (pintype "passive"))
      (node (ref "T8") (pin "B") (pinfunction "B_B") (pintype "passive"))
    )
    (net (code "80") (name "Net-(T1-G)") (class "Default")
      (node (ref "R31") (pin "1") (pinfunction "1_1") (pintype "passive"))
      (node (ref "R48") (pin "2") (pinfunction "2_2") (pintype "passive"))
      (node (ref "T1") (pin "1") (pinfunction "G_1") (pintype "passive"))
    )
    (net (code "81") (name "Net-(T3-E)") (class "Default")
      (node (ref "R4") (pin "2") (pinfunction "2_2") (pintype "passive"))
      (node (ref "SJ1") (pin "1") (pinfunction "1_1") (pintype "passive"))
      (node (ref "T3") (pin "1") (pinfunction "E_1") (pintype "passive"))
      (node (ref "T5") (pin "B") (pinfunction "B_B") (pintype "passive"))
    )
    (net (code "82") (name "Net-(T4-B)") (class "Default")
      (node (ref "R1") (pin "2") (pinfunction "2_2") (pintype "passive"))
      (node (ref "T4") (pin "2") (pinfunction "B_2") (pintype "passive"))
    )
    (net (code "83") (name "Net-(T7-E)") (class "Default")
      (node (ref "R6") (pin "2") (pinfunction "2_2") (pintype "passive"))
      (node (ref "SJ1") (pin "2") (pinfunction "2_2") (pintype "passive"))
      (node (ref "T6") (pin "B") (pinfunction "B_B") (pintype "passive"))
      (node (ref "T7") (pin "1") (pinfunction "E_1") (pintype "passive"))
    )
    (net (code "84") (name "Net-(T9-B)") (class "Default")
      (node (ref "R33") (pin "1") (pinfunction "1_1") (pintype "passive"))
      (node (ref "T9") (pin "1") (pinfunction "B_1") (pintype "passive"))
    )
    (net (code "85") (name "Net-(T9-E)") (class "Default")
      (node (ref "D5") (pin "C") (pinfunction "C_C") (pintype "passive"))
      (node (ref "FAN1") (pin "1") (pinfunction "1_1") (pintype "passive"))
      (node (ref "R17") (pin "1") (pinfunction "1_1") (pintype "passive"))
      (node (ref "T9") (pin "3") (pinfunction "E_3") (pintype "passive"))
    )
    (net (code "86") (name "OVRCRNT_DET") (class "Default")
      (node (ref "C5") (pin "2") (pinfunction "2_2") (pintype "passive"))
      (node (ref "IC13") (pin "3") (pinfunction "+IN_3") (pintype "input"))
      (node (ref "IC2") (pin "7") (pinfunction "OUT_7") (pintype "output"))
      (node (ref "I_PROT") (pin "2") (pinfunction "2_2") (pintype "passive"))
    )
    (net (code "87") (name "OVRCRNT_DET_BUF") (class "Default")
      (node (ref "IC13") (pin "1") (pinfunction "OUT_1") (pintype "output"))
      (node (ref "IC13") (pin "2") (pinfunction "-IN_2") (pintype "input"))
      (node (ref "R23") (pin "2") (pinfunction "2_2") (pintype "passive"))
    )
    (net (code "88") (name "P_VSS") (class "Default")
      (node (ref "C1") (pin "-") (pinfunction "-_-") (pintype "passive"))
      (node (ref "C2") (pin "-") (pinfunction "-_-") (pintype "passive"))
      (node (ref "D17") (pin "1") (pinfunction "A_1") (pintype "passive"))
      (node (ref "D17") (pin "3") (pinfunction "A_3") (pintype "passive"))
      (node (ref "D18") (pin "1") (pinfunction "A_1") (pintype "passive"))
      (node (ref "D18") (pin "3") (pinfunction "A_3") (pintype "passive"))
    )
    (net (code "89") (name "REL-OUT") (class "Default")
      (node (ref "R31") (pin "2") (pinfunction "2_2") (pintype "passive"))
      (node (ref "U$33") (pin "30") (pinfunction "30_30") (pintype "bidirectional"))
    )
    (net (code "90") (name "SCK") (class "Default")
      (node (ref "DSPLY") (pin "4") (pinfunction "4_4") (pintype "passive"))
      (node (ref "IC7") (pin "4") (pinfunction "SCK_4") (pintype "input"))
      (node (ref "R16") (pin "1") (pinfunction "1_1") (pintype "passive"))
    )
    (net (code "91") (name "SENSE") (class "Default")
      (node (ref "R14") (pin "2") (pinfunction "2_2") (pintype "passive"))
      (node (ref "SENSE") (pin "2") (pinfunction "2_2") (pintype "passive"))
    )
    (net (code "92") (name "TH0") (class "Default")
      (node (ref "C49") (pin "2") (pinfunction "2_2") (pintype "passive"))
      (node (ref "R36") (pin "2") (pinfunction "2_2") (pintype "passive"))
      (node (ref "R42") (pin "2") (pinfunction "2_2") (pintype "passive"))
      (node (ref "U$33") (pin "35/A16") (pinfunction "35/A16_35/A16") (pintype "bidirectional"))
    )
    (net (code "93") (name "VSET") (class "Default")
      (node (ref "IC2") (pin "3") (pinfunction "+IN_3") (pintype "input"))
      (node (ref "IC7") (pin "10") (pinfunction "VOUTB_10") (pintype "output"))
    )
    (net (code "94") (name "VSS") (class "Default")
      (node (ref "C10") (pin "-") (pinfunction "-_-") (pintype "passive"))
      (node (ref "C12") (pin "-") (pinfunction "-_-") (pintype "passive"))
      (node (ref "C14") (pin "2") (pinfunction "2_2") (pintype "passive"))
      (node (ref "C16") (pin "2") (pinfunction "2_2") (pintype "passive"))
      (node (ref "C17") (pin "1") (pinfunction "1_1") (pintype "passive"))
      (node (ref "C18") (pin "2") (pinfunction "2_2") (pintype "passive"))
      (node (ref "C19") (pin "2") (pinfunction "2_2") (pintype "passive"))
      (node (ref "C20") (pin "2") (pinfunction "2_2") (pintype "passive"))
      (node (ref "C21") (pin "2") (pinfunction "2_2") (pintype "passive"))
      (node (ref "C23") (pin "2") (pinfunction "2_2") (pintype "passive"))
      (node (ref "C24") (pin "2") (pinfunction "2_2") (pintype "passive"))
      (node (ref "C30") (pin "2") (pinfunction "2_2") (pintype "passive"))
      (node (ref "C31") (pin "2") (pinfunction "2_2") (pintype "passive"))
      (node (ref "C32") (pin "2") (pinfunction "2_2") (pintype "passive"))
      (node (ref "C33") (pin "2") (pinfunction "2_2") (pintype "passive"))
      (node (ref "C34") (pin "-") (pinfunction "-_-") (pintype "passive"))
      (node (ref "C37") (pin "-") (pinfunction "-_-") (pintype "passive"))
      (node (ref "C38") (pin "2") (pinfunction "2_2") (pintype "passive"))
      (node (ref "C39") (pin "1") (pinfunction "1_1") (pintype "passive"))
      (node (ref "C40") (pin "2") (pinfunction "2_2") (pintype "passive"))
      (node (ref "C41") (pin "2") (pinfunction "2_2") (pintype "passive"))
      (node (ref "D19") (pin "+") (pinfunction "A_+") (pintype "passive"))
      (node (ref "D5") (pin "A") (pinfunction "A_A") (pintype "passive"))
      (node (ref "DSPLY") (pin "1") (pinfunction "1_1") (pintype "passive"))
      (node (ref "ESP") (pin "6") (pinfunction "6_6") (pintype "passive"))
      (node (ref "FAN1") (pin "2") (pinfunction "2_2") (pintype "passive"))
      (node (ref "IC1") (pin "2") (pinfunction "GND_2") (pintype "passive"))
      (node (ref "IC15") (pin "1") (pinfunction "GND_1") (pintype "passive"))
      (node (ref "IC18") (pin "2") (pinfunction "GND_2") (pintype "passive"))
      (node (ref "IC4") (pin "4") (pinfunction "V-_4") (pintype "power_in"))
      (node (ref "IC6") (pin "6") (pinfunction "GND_6") (pintype "power_in"))
      (node (ref "IC6") (pin "POWERPAD") (pinfunction "GND_POWERPAD") (pintype "power_in"))
      (node (ref "IC6") (pin "PP1") (pinfunction "GND_PP1") (pintype "power_in"))
      (node (ref "IC6") (pin "PP2") (pinfunction "GND_PP2") (pintype "power_in"))
      (node (ref "IC6") (pin "PP3") (pinfunction "GND_PP3") (pintype "power_in"))
      (node (ref "IC6") (pin "PP4") (pinfunction "GND_PP4") (pintype "power_in"))
      (node (ref "R19") (pin "2") (pinfunction "2_2") (pintype "passive"))
      (node (ref "R27") (pin "2") (pinfunction "2_2") (pintype "passive"))
      (node (ref "R34") (pin "1") (pinfunction "1_1") (pintype "passive"))
      (node (ref "R48") (pin "1") (pinfunction "1_1") (pintype "passive"))
      (node (ref "SG1") (pin "-") (pinfunction "2_-") (pintype "passive"))
      (node (ref "T1") (pin "3") (pinfunction "S_3") (pintype "passive"))
      (node (ref "U$33") (pin "GND") (pinfunction "GND_GND") (pintype "bidirectional"))
      (node (ref "VSS") (pin "MP") (pinfunction "MP_MP") (pintype "passive"))
    )
    (net (code "95") (name "V_OUT_CON") (class "Default")
      (node (ref "REL1") (pin "S1") (pinfunction "S_S1") (pintype "passive"))
      (node (ref "VOUT") (pin "1") (pinfunction "1_1") (pintype "passive"))
      (node (ref "VOUT") (pin "2") (pinfunction "2_2") (pintype "passive"))
    )
    (net (code "96") (name "unconnected-(H1-MOUNT-PadB3,3)") (class "Default")
      (node (ref "H1") (pin "B3,3") (pinfunction "MOUNT_B3,3") (pintype "passive"))
    )
    (net (code "97") (name "unconnected-(H2-MOUNT-PadB3,3)") (class "Default")
      (node (ref "H2") (pin "B3,3") (pinfunction "MOUNT_B3,3") (pintype "passive"))
    )
    (net (code "98") (name "unconnected-(H3-MOUNT-PadB3,3)") (class "Default")
      (node (ref "H3") (pin "B3,3") (pinfunction "MOUNT_B3,3") (pintype "passive"))
    )
    (net (code "99") (name "unconnected-(H4-MOUNT-PadB3,3)") (class "Default")
      (node (ref "H4") (pin "B3,3") (pinfunction "MOUNT_B3,3") (pintype "passive"))
    )
    (net (code "100") (name "unconnected-(IC6-ENA-Pad5)") (class "Default")
      (node (ref "IC6") (pin "5") (pinfunction "ENA_5") (pintype "input"))
    )
    (net (code "101") (name "unconnected-(IC6-NC-Pad2)") (class "Default")
      (node (ref "IC6") (pin "2") (pinfunction "NC_2") (pintype "no_connect"))
    )
    (net (code "102") (name "unconnected-(IC6-NC2-Pad3)") (class "Default")
      (node (ref "IC6") (pin "3") (pinfunction "NC2_3") (pintype "no_connect"))
    )
    (net (code "103") (name "unconnected-(REL1B-O-PadO1)") (class "Default")
      (node (ref "REL1") (pin "O1") (pinfunction "O_O1") (pintype "passive"))
    )
    (net (code "104") (name "unconnected-(REL1C-O-PadO2)") (class "Default")
      (node (ref "REL1") (pin "O2") (pinfunction "O_O2") (pintype "passive"))
    )
    (net (code "105") (name "unconnected-(SENSE-Pad1)") (class "Default")
      (node (ref "SENSE") (pin "1") (pinfunction "1_1") (pintype "passive"))
    )
    (net (code "106") (name "unconnected-(U$33-A21{slash}DAC0-Pad21{slash}DAC0)") (class "Default")
      (node (ref "U$33") (pin "21/DAC0") (pinfunction "A21/DAC0_21/DAC0") (pintype "bidirectional"))
    )
    (net (code "107") (name "unconnected-(U$33-Pad0{slash}RX)") (class "Default")
      (node (ref "U$33") (pin "0/RX") (pinfunction "0/RX_0/RX") (pintype "bidirectional"))
    )
    (net (code "108") (name "unconnected-(U$33-Pad1{slash}TX)") (class "Default")
      (node (ref "U$33") (pin "1/TX") (pinfunction "1/TX_1/TX") (pintype "bidirectional"))
    )
    (net (code "109") (name "unconnected-(U$33-Pad3V3)") (class "Default")
      (node (ref "U$33") (pin "3V3") (pinfunction "3V3_3V3") (pintype "bidirectional"))
    )
    (net (code "110") (name "unconnected-(U$33-Pad3V3_2)") (class "Default")
      (node (ref "U$33") (pin "3V3_2") (pinfunction "3V3_2_3V3_2") (pintype "bidirectional"))
    )
    (net (code "111") (name "unconnected-(U$33-Pad3V3_LO)") (class "Default")
      (node (ref "U$33") (pin "3V3_LO") (pinfunction "3V3_LO_3V3_LO") (pintype "bidirectional"))
    )
    (net (code "112") (name "unconnected-(U$33-Pad5)") (class "Default")
      (node (ref "U$33") (pin "5") (pinfunction "5_5") (pintype "bidirectional"))
    )
    (net (code "113") (name "unconnected-(U$33-Pad6)") (class "Default")
      (node (ref "U$33") (pin "6") (pinfunction "6_6") (pintype "bidirectional"))
    )
    (net (code "114") (name "unconnected-(U$33-Pad7)") (class "Default")
      (node (ref "U$33") (pin "7") (pinfunction "7_7") (pintype "bidirectional"))
    )
    (net (code "115") (name "unconnected-(U$33-Pad9{slash}CS)") (class "Default")
      (node (ref "U$33") (pin "9/CS") (pinfunction "9/CS_9/CS") (pintype "bidirectional"))
    )
    (net (code "116") (name "unconnected-(U$33-Pad13{slash}SCK)") (class "Default")
      (node (ref "U$33") (pin "13/SCK") (pinfunction "13/SCK_13/SCK") (pintype "bidirectional"))
    )
    (net (code "117") (name "unconnected-(U$33-Pad15{slash}A1)") (class "Default")
      (node (ref "U$33") (pin "15/A1") (pinfunction "15/A1_15/A1") (pintype "bidirectional"))
    )
    (net (code "118") (name "unconnected-(U$33-Pad16{slash}A2)") (class "Default")
      (node (ref "U$33") (pin "16/A2") (pinfunction "16/A2_16/A2") (pintype "bidirectional"))
    )
    (net (code "119") (name "unconnected-(U$33-Pad17{slash}A3)") (class "Default")
      (node (ref "U$33") (pin "17/A3") (pinfunction "17/A3_17/A3") (pintype "bidirectional"))
    )
    (net (code "120") (name "unconnected-(U$33-Pad18{slash}A4{slash}SDA)") (class "Default")
      (node (ref "U$33") (pin "18/A4/SDA") (pinfunction "18/A4/SDA_18/A4/SDA") (pintype "bidirectional"))
    )
    (net (code "121") (name "unconnected-(U$33-Pad25)") (class "Default")
      (node (ref "U$33") (pin "25") (pinfunction "25_25") (pintype "bidirectional"))
    )
    (net (code "122") (name "unconnected-(U$33-PadA10)") (class "Default")
      (node (ref "U$33") (pin "A10") (pinfunction "A10_A10") (pintype "bidirectional"))
    )
    (net (code "123") (name "unconnected-(U$33-PadA11)") (class "Default")
      (node (ref "U$33") (pin "A11") (pinfunction "A11_A11") (pintype "bidirectional"))
    )
    (net (code "124") (name "unconnected-(U$33-PadGND2)") (class "Default")
      (node (ref "U$33") (pin "GND2") (pinfunction "GND2_GND2") (pintype "bidirectional"))
    )
    (net (code "125") (name "unconnected-(U$33-PadGND3)") (class "Default")
      (node (ref "U$33") (pin "GND3") (pinfunction "GND3_GND3") (pintype "bidirectional"))
    )
    (net (code "126") (name "unconnected-(U$33-PadPROG)") (class "Default")
      (node (ref "U$33") (pin "PROG") (pinfunction "PROG_PROG") (pintype "bidirectional"))
    )
    (net (code "127") (name "unconnected-(U$33-PadRESET)") (class "Default")
      (node (ref "U$33") (pin "RESET") (pinfunction "RESET_RESET") (pintype "bidirectional"))
    )
    (net (code "128") (name "unconnected-(U$33-PadU5V)") (class "Default")
      (node (ref "U$33") (pin "U5V") (pinfunction "U5V_U5V") (pintype "bidirectional"))
    )
    (net (code "129") (name "unconnected-(U$33-PadUD+)") (class "Default")
      (node (ref "U$33") (pin "UD+") (pinfunction "UD+_UD+") (pintype "bidirectional"))
    )
    (net (code "130") (name "unconnected-(U$33-PadUD-)") (class "Default")
      (node (ref "U$33") (pin "UD-") (pinfunction "UD-_UD-") (pintype "bidirectional"))
    )
    (net (code "131") (name "unconnected-(U$33-PadUGND1)") (class "Default")
      (node (ref "U$33") (pin "UGND1") (pinfunction "UGND1_UGND1") (pintype "bidirectional"))
    )
    (net (code "132") (name "unconnected-(U$33-PadUGND2)") (class "Default")
      (node (ref "U$33") (pin "UGND2") (pinfunction "UGND2_UGND2") (pintype "bidirectional"))
    )
    (net (code "133") (name "unconnected-(U$33-PadVBAT)") (class "Default")
      (node (ref "U$33") (pin "VBAT") (pinfunction "VBAT_VBAT") (pintype "bidirectional"))
    )
    (net (code "134") (name "unconnected-(U$33-PadVUSB)") (class "Default")
      (node (ref "U$33") (pin "VUSB") (pinfunction "VUSB_VUSB") (pintype "bidirectional"))
    )
    (net (code "135") (name "unconnected-(V_SEL-Pad1)") (class "Default")
      (node (ref "V_SEL") (pin "1") (pinfunction "1_1") (pintype "passive"))
    )
  )
)
